# uac.net
KiCad netlist of a schematic drawn in EAGLE
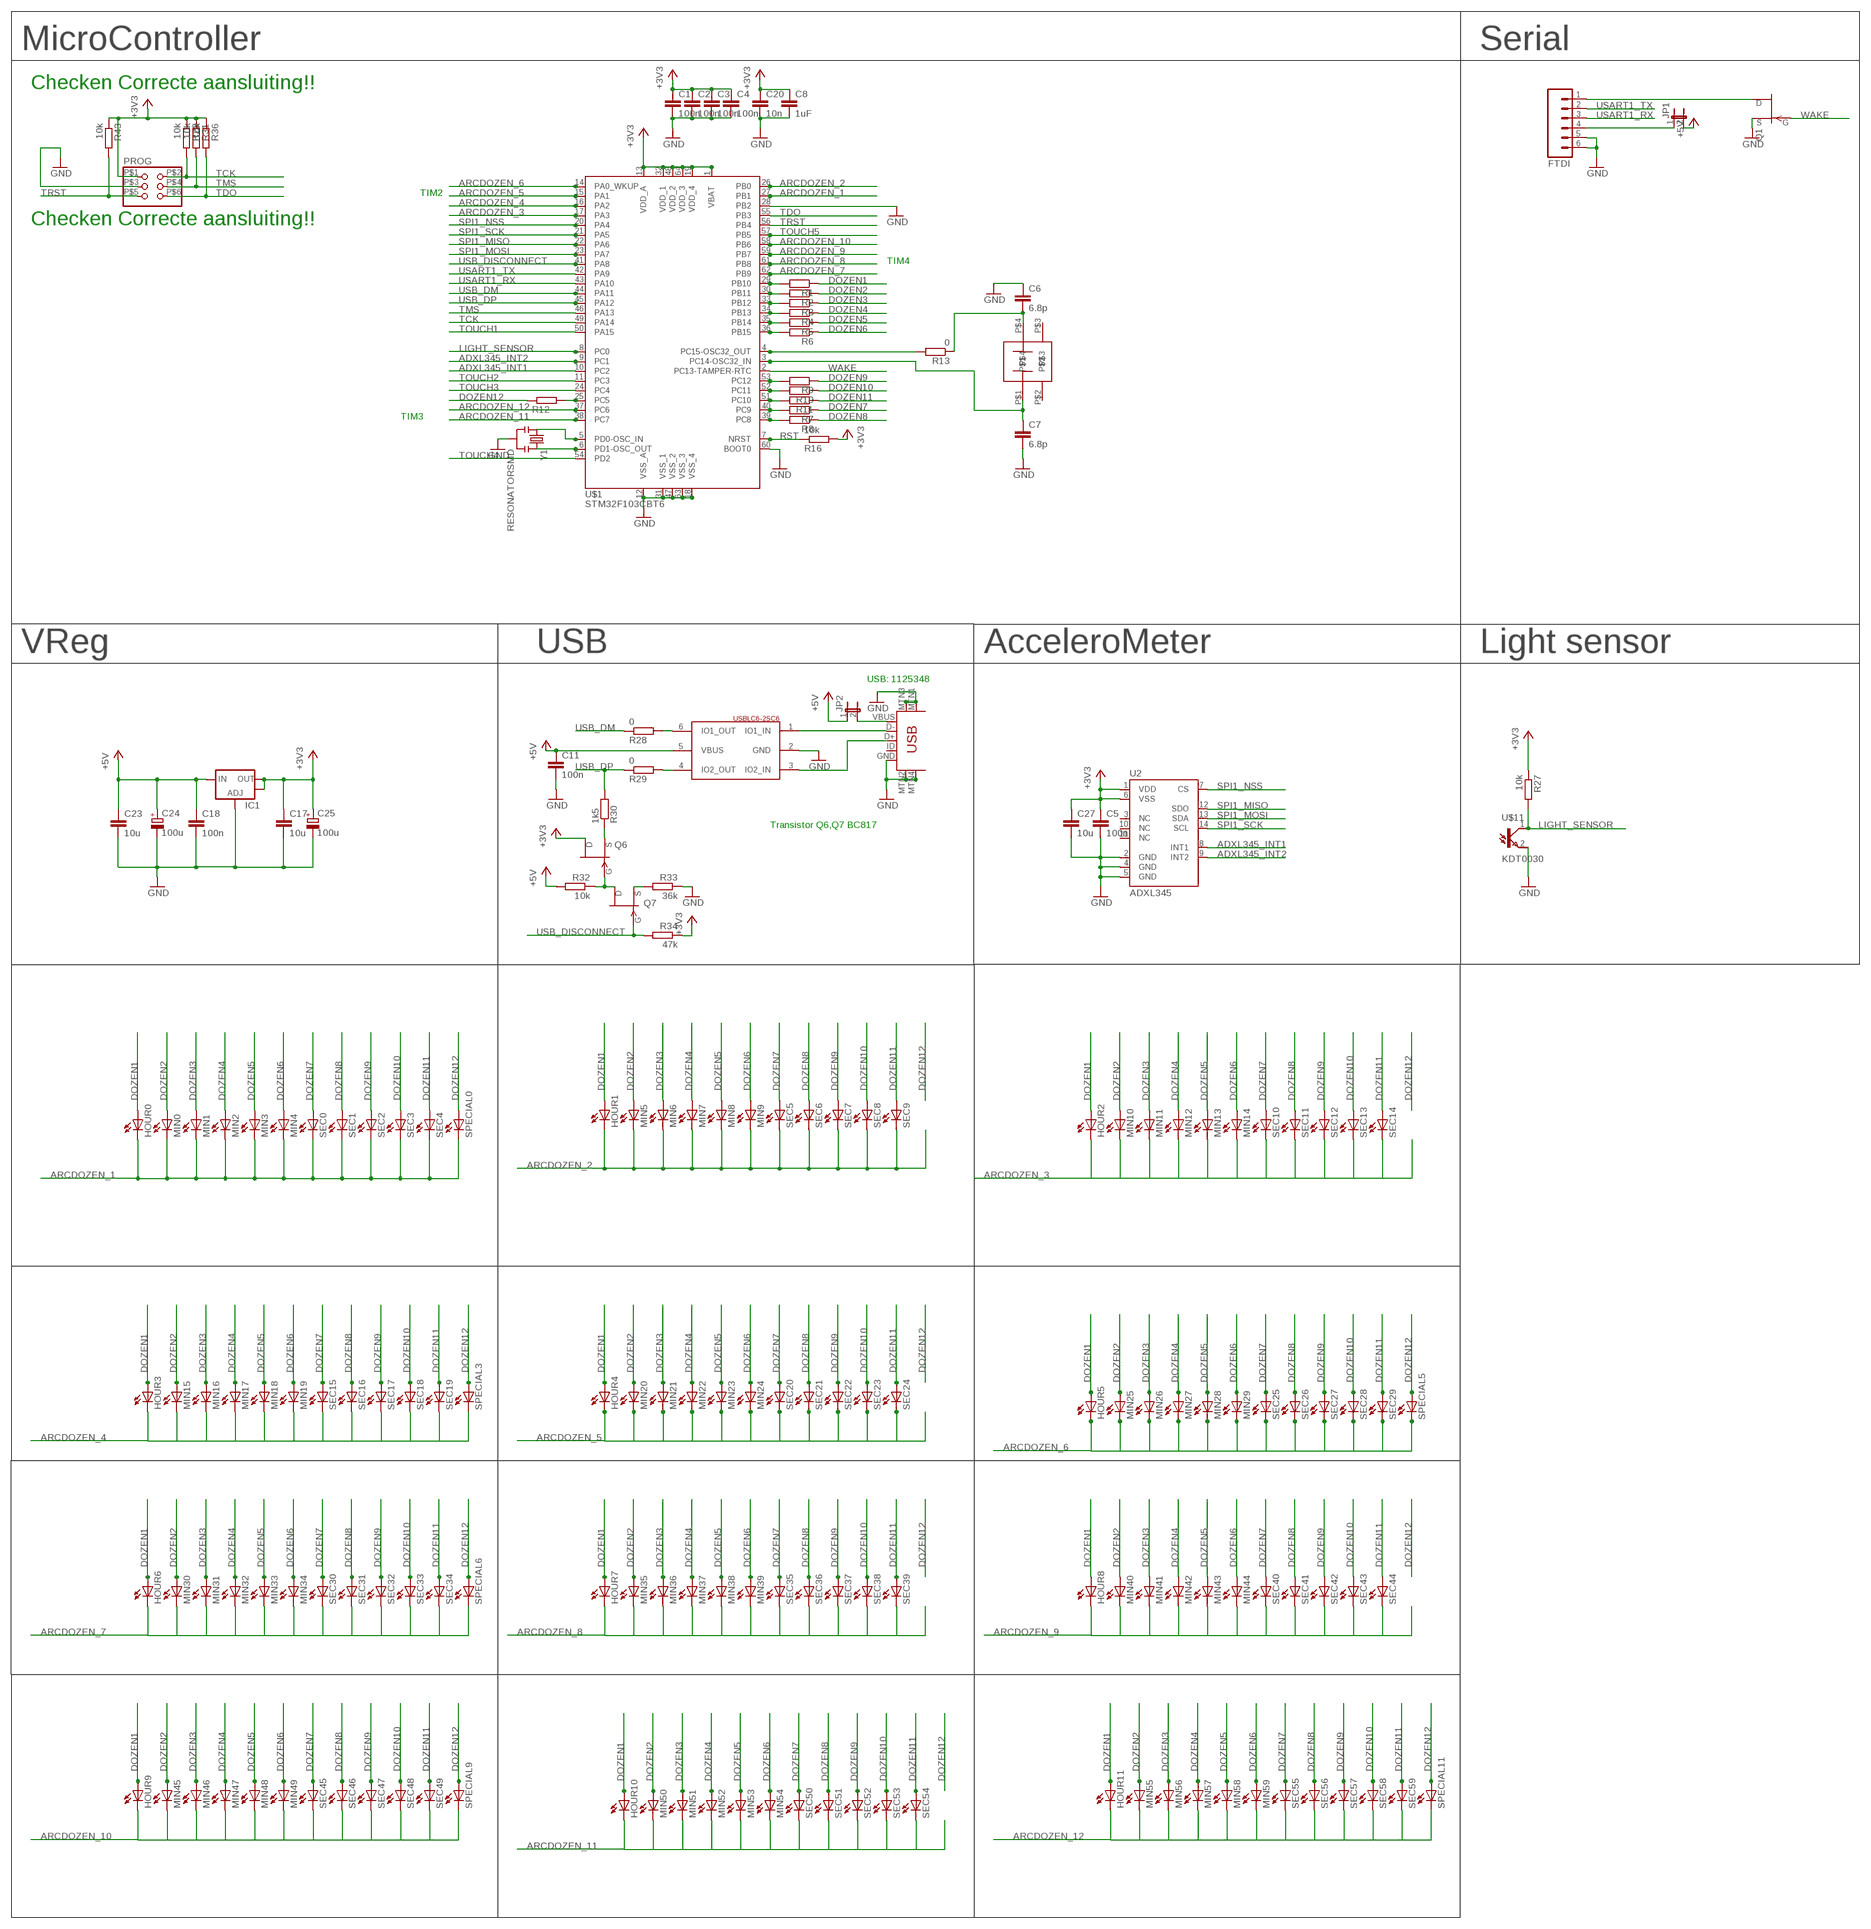
[diagram p0: schematic, sheet 1]

(export (version "E")
  (design (tool "Eeschema 10.0.6"))
  (components
    (comp (ref "C1")
      (value "100n")
      (footprint "eagle-import:C0603")
      (libsource (lib "eagle-import") (part "C-EUC0603"))
    )
    (comp (ref "C2")
      (value "100n")
      (footprint "eagle-import:C0603")
      (libsource (lib "eagle-import") (part "C-EUC0603"))
    )
    (comp (ref "C3")
      (value "100n")
      (footprint "eagle-import:C0603")
      (libsource (lib "eagle-import") (part "C-EUC0603"))
    )
    (comp (ref "C4")
      (value "100n")
      (footprint "eagle-import:C0603")
      (libsource (lib "eagle-import") (part "C-EUC0603"))
    )
    (comp (ref "C5")
      (value "100n")
      (footprint "eagle-import:C0603")
      (libsource (lib "eagle-import") (part "C-EUC0603"))
    )
    (comp (ref "C6")
      (value "6.8p")
      (footprint "eagle-import:C0603")
      (libsource (lib "eagle-import") (part "C-EUC0603"))
    )
    (comp (ref "C7")
      (value "6.8p")
      (footprint "eagle-import:C0603")
      (libsource (lib "eagle-import") (part "C-EUC0603"))
    )
    (comp (ref "C8")
      (value "1uF")
      (footprint "eagle-import:C0603")
      (libsource (lib "eagle-import") (part "C-EUC0603"))
    )
    (comp (ref "C11")
      (value "100n")
      (footprint "eagle-import:C0603")
      (libsource (lib "eagle-import") (part "C-EUC0603"))
    )
    (comp (ref "C17")
      (value "10u")
      (footprint "eagle-import:C0603")
      (libsource (lib "eagle-import") (part "C-EUC0603"))
    )
    (comp (ref "C18")
      (value "100n")
      (footprint "eagle-import:C0603")
      (libsource (lib "eagle-import") (part "C-EUC0603"))
    )
    (comp (ref "C20")
      (value "10n")
      (footprint "eagle-import:C0603")
      (libsource (lib "eagle-import") (part "C-EUC0603"))
    )
    (comp (ref "C23")
      (value "10u")
      (footprint "eagle-import:C0603")
      (libsource (lib "eagle-import") (part "C-EUC0603"))
    )
    (comp (ref "C24")
      (value "100u")
      (footprint "eagle-import:SMC_C")
      (libsource (lib "eagle-import") (part "CPOL-EUSMCC"))
    )
    (comp (ref "C25")
      (value "100u")
      (footprint "eagle-import:SMC_C")
      (libsource (lib "eagle-import") (part "CPOL-EUSMCC"))
    )
    (comp (ref "C27")
      (value "10u")
      (footprint "eagle-import:C0603")
      (libsource (lib "eagle-import") (part "C-EUC0603"))
    )
    (comp (ref "FTDI")
      (value "M06SMD")
      (footprint "eagle-import:1X06-SMD")
      (libsource (lib "eagle-import") (part "M06SMD"))
    )
    (comp (ref "HOUR0")
      (value "LEDCHIPLED_0603")
      (footprint "eagle-import:CHIPLED_0603")
      (libsource (lib "eagle-import") (part "LEDCHIPLED_0603"))
    )
    (comp (ref "HOUR1")
      (value "LEDCHIPLED_0603")
      (footprint "eagle-import:CHIPLED_0603")
      (libsource (lib "eagle-import") (part "LEDCHIPLED_0603"))
    )
    (comp (ref "HOUR2")
      (value "LEDCHIPLED_0603")
      (footprint "eagle-import:CHIPLED_0603")
      (libsource (lib "eagle-import") (part "LEDCHIPLED_0603"))
    )
    (comp (ref "HOUR3")
      (value "LEDCHIPLED_0603")
      (footprint "eagle-import:CHIPLED_0603")
      (libsource (lib "eagle-import") (part "LEDCHIPLED_0603"))
    )
    (comp (ref "HOUR4")
      (value "LEDCHIPLED_0603")
      (footprint "eagle-import:CHIPLED_0603")
      (libsource (lib "eagle-import") (part "LEDCHIPLED_0603"))
    )
    (comp (ref "HOUR5")
      (value "LEDCHIPLED_0603")
      (footprint "eagle-import:CHIPLED_0603")
      (libsource (lib "eagle-import") (part "LEDCHIPLED_0603"))
    )
    (comp (ref "HOUR6")
      (value "LEDCHIPLED_0603")
      (footprint "eagle-import:CHIPLED_0603")
      (libsource (lib "eagle-import") (part "LEDCHIPLED_0603"))
    )
    (comp (ref "HOUR7")
      (value "LEDCHIPLED_0603")
      (footprint "eagle-import:CHIPLED_0603")
      (libsource (lib "eagle-import") (part "LEDCHIPLED_0603"))
    )
    (comp (ref "HOUR8")
      (value "LEDCHIPLED_0603")
      (footprint "eagle-import:CHIPLED_0603")
      (libsource (lib "eagle-import") (part "LEDCHIPLED_0603"))
    )
    (comp (ref "HOUR9")
      (value "LEDCHIPLED_0603")
      (footprint "eagle-import:CHIPLED_0603")
      (libsource (lib "eagle-import") (part "LEDCHIPLED_0603"))
    )
    (comp (ref "HOUR10")
      (value "LEDCHIPLED_0603")
      (footprint "eagle-import:CHIPLED_0603")
      (libsource (lib "eagle-import") (part "LEDCHIPLED_0603"))
    )
    (comp (ref "HOUR11")
      (value "LEDCHIPLED_0603")
      (footprint "eagle-import:CHIPLED_0603")
      (libsource (lib "eagle-import") (part "LEDCHIPLED_0603"))
    )
    (comp (ref "IC1")
      (value "V_REG_LM1117SOT223")
      (footprint "eagle-import:SOT223")
      (libsource (lib "eagle-import") (part "V_REG_LM1117SOT223"))
    )
    (comp (ref "JP1")
      (value "JUMPER-2SMD-NO")
      (footprint "eagle-import:SJ_2S-NO")
      (libsource (lib "eagle-import") (part "JUMPER-2SMD-NO"))
    )
    (comp (ref "JP2")
      (value "JUMPER-2SMD-NO")
      (footprint "eagle-import:SJ_2S-NO")
      (libsource (lib "eagle-import") (part "JUMPER-2SMD-NO"))
    )
    (comp (ref "MIN0")
      (value "LEDCHIPLED_0603")
      (footprint "eagle-import:CHIPLED_0603")
      (libsource (lib "eagle-import") (part "LEDCHIPLED_0603"))
    )
    (comp (ref "MIN1")
      (value "LEDCHIPLED_0603")
      (footprint "eagle-import:CHIPLED_0603")
      (libsource (lib "eagle-import") (part "LEDCHIPLED_0603"))
    )
    (comp (ref "MIN2")
      (value "LEDCHIPLED_0603")
      (footprint "eagle-import:CHIPLED_0603")
      (libsource (lib "eagle-import") (part "LEDCHIPLED_0603"))
    )
    (comp (ref "MIN3")
      (value "LEDCHIPLED_0603")
      (footprint "eagle-import:CHIPLED_0603")
      (libsource (lib "eagle-import") (part "LEDCHIPLED_0603"))
    )
    (comp (ref "MIN4")
      (value "LEDCHIPLED_0603")
      (footprint "eagle-import:CHIPLED_0603")
      (libsource (lib "eagle-import") (part "LEDCHIPLED_0603"))
    )
    (comp (ref "MIN5")
      (value "LEDCHIPLED_0603")
      (footprint "eagle-import:CHIPLED_0603")
      (libsource (lib "eagle-import") (part "LEDCHIPLED_0603"))
    )
    (comp (ref "MIN6")
      (value "LEDCHIPLED_0603")
      (footprint "eagle-import:CHIPLED_0603")
      (libsource (lib "eagle-import") (part "LEDCHIPLED_0603"))
    )
    (comp (ref "MIN7")
      (value "LEDCHIPLED_0603")
      (footprint "eagle-import:CHIPLED_0603")
      (libsource (lib "eagle-import") (part "LEDCHIPLED_0603"))
    )
    (comp (ref "MIN8")
      (value "LEDCHIPLED_0603")
      (footprint "eagle-import:CHIPLED_0603")
      (libsource (lib "eagle-import") (part "LEDCHIPLED_0603"))
    )
    (comp (ref "MIN9")
      (value "LEDCHIPLED_0603")
      (footprint "eagle-import:CHIPLED_0603")
      (libsource (lib "eagle-import") (part "LEDCHIPLED_0603"))
    )
    (comp (ref "MIN10")
      (value "LEDCHIPLED_0603")
      (footprint "eagle-import:CHIPLED_0603")
      (libsource (lib "eagle-import") (part "LEDCHIPLED_0603"))
    )
    (comp (ref "MIN11")
      (value "LEDCHIPLED_0603")
      (footprint "eagle-import:CHIPLED_0603")
      (libsource (lib "eagle-import") (part "LEDCHIPLED_0603"))
    )
    (comp (ref "MIN12")
      (value "LEDCHIPLED_0603")
      (footprint "eagle-import:CHIPLED_0603")
      (libsource (lib "eagle-import") (part "LEDCHIPLED_0603"))
    )
    (comp (ref "MIN13")
      (value "LEDCHIPLED_0603")
      (footprint "eagle-import:CHIPLED_0603")
      (libsource (lib "eagle-import") (part "LEDCHIPLED_0603"))
    )
    (comp (ref "MIN14")
      (value "LEDCHIPLED_0603")
      (footprint "eagle-import:CHIPLED_0603")
      (libsource (lib "eagle-import") (part "LEDCHIPLED_0603"))
    )
    (comp (ref "MIN15")
      (value "LEDCHIPLED_0603")
      (footprint "eagle-import:CHIPLED_0603")
      (libsource (lib "eagle-import") (part "LEDCHIPLED_0603"))
    )
    (comp (ref "MIN16")
      (value "LEDCHIPLED_0603")
      (footprint "eagle-import:CHIPLED_0603")
      (libsource (lib "eagle-import") (part "LEDCHIPLED_0603"))
    )
    (comp (ref "MIN17")
      (value "LEDCHIPLED_0603")
      (footprint "eagle-import:CHIPLED_0603")
      (libsource (lib "eagle-import") (part "LEDCHIPLED_0603"))
    )
    (comp (ref "MIN18")
      (value "LEDCHIPLED_0603")
      (footprint "eagle-import:CHIPLED_0603")
      (libsource (lib "eagle-import") (part "LEDCHIPLED_0603"))
    )
    (comp (ref "MIN19")
      (value "LEDCHIPLED_0603")
      (footprint "eagle-import:CHIPLED_0603")
      (libsource (lib "eagle-import") (part "LEDCHIPLED_0603"))
    )
    (comp (ref "MIN20")
      (value "LEDCHIPLED_0603")
      (footprint "eagle-import:CHIPLED_0603")
      (libsource (lib "eagle-import") (part "LEDCHIPLED_0603"))
    )
    (comp (ref "MIN21")
      (value "LEDCHIPLED_0603")
      (footprint "eagle-import:CHIPLED_0603")
      (libsource (lib "eagle-import") (part "LEDCHIPLED_0603"))
    )
    (comp (ref "MIN22")
      (value "LEDCHIPLED_0603")
      (footprint "eagle-import:CHIPLED_0603")
      (libsource (lib "eagle-import") (part "LEDCHIPLED_0603"))
    )
    (comp (ref "MIN23")
      (value "LEDCHIPLED_0603")
      (footprint "eagle-import:CHIPLED_0603")
      (libsource (lib "eagle-import") (part "LEDCHIPLED_0603"))
    )
    (comp (ref "MIN24")
      (value "LEDCHIPLED_0603")
      (footprint "eagle-import:CHIPLED_0603")
      (libsource (lib "eagle-import") (part "LEDCHIPLED_0603"))
    )
    (comp (ref "MIN25")
      (value "LEDCHIPLED_0603")
      (footprint "eagle-import:CHIPLED_0603")
      (libsource (lib "eagle-import") (part "LEDCHIPLED_0603"))
    )
    (comp (ref "MIN26")
      (value "LEDCHIPLED_0603")
      (footprint "eagle-import:CHIPLED_0603")
      (libsource (lib "eagle-import") (part "LEDCHIPLED_0603"))
    )
    (comp (ref "MIN27")
      (value "LEDCHIPLED_0603")
      (footprint "eagle-import:CHIPLED_0603")
      (libsource (lib "eagle-import") (part "LEDCHIPLED_0603"))
    )
    (comp (ref "MIN28")
      (value "LEDCHIPLED_0603")
      (footprint "eagle-import:CHIPLED_0603")
      (libsource (lib "eagle-import") (part "LEDCHIPLED_0603"))
    )
    (comp (ref "MIN29")
      (value "LEDCHIPLED_0603")
      (footprint "eagle-import:CHIPLED_0603")
      (libsource (lib "eagle-import") (part "LEDCHIPLED_0603"))
    )
    (comp (ref "MIN30")
      (value "LEDCHIPLED_0603")
      (footprint "eagle-import:CHIPLED_0603")
      (libsource (lib "eagle-import") (part "LEDCHIPLED_0603"))
    )
    (comp (ref "MIN31")
      (value "LEDCHIPLED_0603")
      (footprint "eagle-import:CHIPLED_0603")
      (libsource (lib "eagle-import") (part "LEDCHIPLED_0603"))
    )
    (comp (ref "MIN32")
      (value "LEDCHIPLED_0603")
      (footprint "eagle-import:CHIPLED_0603")
      (libsource (lib "eagle-import") (part "LEDCHIPLED_0603"))
    )
    (comp (ref "MIN33")
      (value "LEDCHIPLED_0603")
      (footprint "eagle-import:CHIPLED_0603")
      (libsource (lib "eagle-import") (part "LEDCHIPLED_0603"))
    )
    (comp (ref "MIN34")
      (value "LEDCHIPLED_0603")
      (footprint "eagle-import:CHIPLED_0603")
      (libsource (lib "eagle-import") (part "LEDCHIPLED_0603"))
    )
    (comp (ref "MIN35")
      (value "LEDCHIPLED_0603")
      (footprint "eagle-import:CHIPLED_0603")
      (libsource (lib "eagle-import") (part "LEDCHIPLED_0603"))
    )
    (comp (ref "MIN36")
      (value "LEDCHIPLED_0603")
      (footprint "eagle-import:CHIPLED_0603")
      (libsource (lib "eagle-import") (part "LEDCHIPLED_0603"))
    )
    (comp (ref "MIN37")
      (value "LEDCHIPLED_0603")
      (footprint "eagle-import:CHIPLED_0603")
      (libsource (lib "eagle-import") (part "LEDCHIPLED_0603"))
    )
    (comp (ref "MIN38")
      (value "LEDCHIPLED_0603")
      (footprint "eagle-import:CHIPLED_0603")
      (libsource (lib "eagle-import") (part "LEDCHIPLED_0603"))
    )
    (comp (ref "MIN39")
      (value "LEDCHIPLED_0603")
      (footprint "eagle-import:CHIPLED_0603")
      (libsource (lib "eagle-import") (part "LEDCHIPLED_0603"))
    )
    (comp (ref "MIN40")
      (value "LEDCHIPLED_0603")
      (footprint "eagle-import:CHIPLED_0603")
      (libsource (lib "eagle-import") (part "LEDCHIPLED_0603"))
    )
    (comp (ref "MIN41")
      (value "LEDCHIPLED_0603")
      (footprint "eagle-import:CHIPLED_0603")
      (libsource (lib "eagle-import") (part "LEDCHIPLED_0603"))
    )
    (comp (ref "MIN42")
      (value "LEDCHIPLED_0603")
      (footprint "eagle-import:CHIPLED_0603")
      (libsource (lib "eagle-import") (part "LEDCHIPLED_0603"))
    )
    (comp (ref "MIN43")
      (value "LEDCHIPLED_0603")
      (footprint "eagle-import:CHIPLED_0603")
      (libsource (lib "eagle-import") (part "LEDCHIPLED_0603"))
    )
    (comp (ref "MIN44")
      (value "LEDCHIPLED_0603")
      (footprint "eagle-import:CHIPLED_0603")
      (libsource (lib "eagle-import") (part "LEDCHIPLED_0603"))
    )
    (comp (ref "MIN45")
      (value "LEDCHIPLED_0603")
      (footprint "eagle-import:CHIPLED_0603")
      (libsource (lib "eagle-import") (part "LEDCHIPLED_0603"))
    )
    (comp (ref "MIN46")
      (value "LEDCHIPLED_0603")
      (footprint "eagle-import:CHIPLED_0603")
      (libsource (lib "eagle-import") (part "LEDCHIPLED_0603"))
    )
    (comp (ref "MIN47")
      (value "LEDCHIPLED_0603")
      (footprint "eagle-import:CHIPLED_0603")
      (libsource (lib "eagle-import") (part "LEDCHIPLED_0603"))
    )
    (comp (ref "MIN48")
      (value "LEDCHIPLED_0603")
      (footprint "eagle-import:CHIPLED_0603")
      (libsource (lib "eagle-import") (part "LEDCHIPLED_0603"))
    )
    (comp (ref "MIN49")
      (value "LEDCHIPLED_0603")
      (footprint "eagle-import:CHIPLED_0603")
      (libsource (lib "eagle-import") (part "LEDCHIPLED_0603"))
    )
    (comp (ref "MIN50")
      (value "LEDCHIPLED_0603")
      (footprint "eagle-import:CHIPLED_0603")
      (libsource (lib "eagle-import") (part "LEDCHIPLED_0603"))
    )
    (comp (ref "MIN51")
      (value "LEDCHIPLED_0603")
      (footprint "eagle-import:CHIPLED_0603")
      (libsource (lib "eagle-import") (part "LEDCHIPLED_0603"))
    )
    (comp (ref "MIN52")
      (value "LEDCHIPLED_0603")
      (footprint "eagle-import:CHIPLED_0603")
      (libsource (lib "eagle-import") (part "LEDCHIPLED_0603"))
    )
    (comp (ref "MIN53")
      (value "LEDCHIPLED_0603")
      (footprint "eagle-import:CHIPLED_0603")
      (libsource (lib "eagle-import") (part "LEDCHIPLED_0603"))
    )
    (comp (ref "MIN54")
      (value "LEDCHIPLED_0603")
      (footprint "eagle-import:CHIPLED_0603")
      (libsource (lib "eagle-import") (part "LEDCHIPLED_0603"))
    )
    (comp (ref "MIN55")
      (value "LEDCHIPLED_0603")
      (footprint "eagle-import:CHIPLED_0603")
      (libsource (lib "eagle-import") (part "LEDCHIPLED_0603"))
    )
    (comp (ref "MIN56")
      (value "LEDCHIPLED_0603")
      (footprint "eagle-import:CHIPLED_0603")
      (libsource (lib "eagle-import") (part "LEDCHIPLED_0603"))
    )
    (comp (ref "MIN57")
      (value "LEDCHIPLED_0603")
      (footprint "eagle-import:CHIPLED_0603")
      (libsource (lib "eagle-import") (part "LEDCHIPLED_0603"))
    )
    (comp (ref "MIN58")
      (value "LEDCHIPLED_0603")
      (footprint "eagle-import:CHIPLED_0603")
      (libsource (lib "eagle-import") (part "LEDCHIPLED_0603"))
    )
    (comp (ref "MIN59")
      (value "LEDCHIPLED_0603")
      (footprint "eagle-import:CHIPLED_0603")
      (libsource (lib "eagle-import") (part "LEDCHIPLED_0603"))
    )
    (comp (ref "PROG")
      (value "PINHD-2X3SMT")
      (footprint "eagle-import:2X03_SMT")
      (libsource (lib "eagle-import") (part "PINHD-2X3SMT"))
    )
    (comp (ref "Q1")
      (value "2N7002CK4SST")
      (footprint "eagle-import:SOT23")
      (libsource (lib "eagle-import") (part "2N7002CKSST4"))
    )
    (comp (ref "Q6")
      (value "2N7002CK4SST")
      (footprint "eagle-import:SOT23")
      (libsource (lib "eagle-import") (part "2N7002CKSST4"))
    )
    (comp (ref "Q7")
      (value "2N7002CK4SST")
      (footprint "eagle-import:SOT23")
      (libsource (lib "eagle-import") (part "2N7002CKSST4"))
    )
    (comp (ref "R1")
      (value "R-EU_R0603")
      (footprint "eagle-import:R0603")
      (libsource (lib "eagle-import") (part "R-EU_R0603"))
    )
    (comp (ref "R2")
      (value "R-EU_R0603")
      (footprint "eagle-import:R0603")
      (libsource (lib "eagle-import") (part "R-EU_R0603"))
    )
    (comp (ref "R3")
      (value "R-EU_R0603")
      (footprint "eagle-import:R0603")
      (libsource (lib "eagle-import") (part "R-EU_R0603"))
    )
    (comp (ref "R4")
      (value "R-EU_R0603")
      (footprint "eagle-import:R0603")
      (libsource (lib "eagle-import") (part "R-EU_R0603"))
    )
    (comp (ref "R5")
      (value "R-EU_R0603")
      (footprint "eagle-import:R0603")
      (libsource (lib "eagle-import") (part "R-EU_R0603"))
    )
    (comp (ref "R6")
      (value "R-EU_R0603")
      (footprint "eagle-import:R0603")
      (libsource (lib "eagle-import") (part "R-EU_R0603"))
    )
    (comp (ref "R7")
      (value "R-EU_R0603")
      (footprint "eagle-import:R0603")
      (libsource (lib "eagle-import") (part "R-EU_R0603"))
    )
    (comp (ref "R8")
      (value "R-EU_R0603")
      (footprint "eagle-import:R0603")
      (libsource (lib "eagle-import") (part "R-EU_R0603"))
    )
    (comp (ref "R9")
      (value "R-EU_R0603")
      (footprint "eagle-import:R0603")
      (libsource (lib "eagle-import") (part "R-EU_R0603"))
    )
    (comp (ref "R10")
      (value "R-EU_R0603")
      (footprint "eagle-import:R0603")
      (libsource (lib "eagle-import") (part "R-EU_R0603"))
    )
    (comp (ref "R11")
      (value "R-EU_R0603")
      (footprint "eagle-import:R0603")
      (libsource (lib "eagle-import") (part "R-EU_R0603"))
    )
    (comp (ref "R12")
      (value "R-EU_R0603")
      (footprint "eagle-import:R0603")
      (libsource (lib "eagle-import") (part "R-EU_R0603"))
    )
    (comp (ref "R13")
      (value "0")
      (footprint "eagle-import:R0603")
      (libsource (lib "eagle-import") (part "R-EU_R0603"))
    )
    (comp (ref "R16")
      (value "10k")
      (footprint "eagle-import:R0603")
      (libsource (lib "eagle-import") (part "R-EU_R0603"))
    )
    (comp (ref "R23")
      (value "10k")
      (footprint "eagle-import:R0603")
      (libsource (lib "eagle-import") (part "R-EU_R0603"))
    )
    (comp (ref "R27")
      (value "10k")
      (footprint "eagle-import:R0603")
      (libsource (lib "eagle-import") (part "R-EU_R0603"))
    )
    (comp (ref "R28")
      (value "0")
      (footprint "eagle-import:R0603")
      (libsource (lib "eagle-import") (part "R-EU_R0603"))
    )
    (comp (ref "R29")
      (value "0")
      (footprint "eagle-import:R0603")
      (libsource (lib "eagle-import") (part "R-EU_R0603"))
    )
    (comp (ref "R30")
      (value "1k5")
      (footprint "eagle-import:R0603")
      (libsource (lib "eagle-import") (part "R-EU_R0603"))
    )
    (comp (ref "R31")
      (value "10k")
      (footprint "eagle-import:R0603")
      (libsource (lib "eagle-import") (part "R-EU_R0603"))
    )
    (comp (ref "R32")
      (value "10k")
      (footprint "eagle-import:R0603")
      (libsource (lib "eagle-import") (part "R-EU_R0603"))
    )
    (comp (ref "R33")
      (value "36k")
      (footprint "eagle-import:R0603")
      (libsource (lib "eagle-import") (part "R-EU_R0603"))
    )
    (comp (ref "R34")
      (value "47k")
      (footprint "eagle-import:R0603")
      (libsource (lib "eagle-import") (part "R-EU_R0603"))
    )
    (comp (ref "R36")
      (value "10k")
      (footprint "eagle-import:R0603")
      (libsource (lib "eagle-import") (part "R-EU_R0603"))
    )
    (comp (ref "R43")
      (value "10k")
      (footprint "eagle-import:R0603")
      (libsource (lib "eagle-import") (part "R-EU_R0603"))
    )
    (comp (ref "SEC0")
      (value "LEDCHIPLED_0603")
      (footprint "eagle-import:CHIPLED_0603")
      (libsource (lib "eagle-import") (part "LEDCHIPLED_0603"))
    )
    (comp (ref "SEC1")
      (value "LEDCHIPLED_0603")
      (footprint "eagle-import:CHIPLED_0603")
      (libsource (lib "eagle-import") (part "LEDCHIPLED_0603"))
    )
    (comp (ref "SEC2")
      (value "LEDCHIPLED_0603")
      (footprint "eagle-import:CHIPLED_0603")
      (libsource (lib "eagle-import") (part "LEDCHIPLED_0603"))
    )
    (comp (ref "SEC3")
      (value "LEDCHIPLED_0603")
      (footprint "eagle-import:CHIPLED_0603")
      (libsource (lib "eagle-import") (part "LEDCHIPLED_0603"))
    )
    (comp (ref "SEC4")
      (value "LEDCHIPLED_0603")
      (footprint "eagle-import:CHIPLED_0603")
      (libsource (lib "eagle-import") (part "LEDCHIPLED_0603"))
    )
    (comp (ref "SEC5")
      (value "LEDCHIPLED_0603")
      (footprint "eagle-import:CHIPLED_0603")
      (libsource (lib "eagle-import") (part "LEDCHIPLED_0603"))
    )
    (comp (ref "SEC6")
      (value "LEDCHIPLED_0603")
      (footprint "eagle-import:CHIPLED_0603")
      (libsource (lib "eagle-import") (part "LEDCHIPLED_0603"))
    )
    (comp (ref "SEC7")
      (value "LEDCHIPLED_0603")
      (footprint "eagle-import:CHIPLED_0603")
      (libsource (lib "eagle-import") (part "LEDCHIPLED_0603"))
    )
    (comp (ref "SEC8")
      (value "LEDCHIPLED_0603")
      (footprint "eagle-import:CHIPLED_0603")
      (libsource (lib "eagle-import") (part "LEDCHIPLED_0603"))
    )
    (comp (ref "SEC9")
      (value "LEDCHIPLED_0603")
      (footprint "eagle-import:CHIPLED_0603")
      (libsource (lib "eagle-import") (part "LEDCHIPLED_0603"))
    )
    (comp (ref "SEC10")
      (value "LEDCHIPLED_0603")
      (footprint "eagle-import:CHIPLED_0603")
      (libsource (lib "eagle-import") (part "LEDCHIPLED_0603"))
    )
    (comp (ref "SEC11")
      (value "LEDCHIPLED_0603")
      (footprint "eagle-import:CHIPLED_0603")
      (libsource (lib "eagle-import") (part "LEDCHIPLED_0603"))
    )
    (comp (ref "SEC12")
      (value "LEDCHIPLED_0603")
      (footprint "eagle-import:CHIPLED_0603")
      (libsource (lib "eagle-import") (part "LEDCHIPLED_0603"))
    )
    (comp (ref "SEC13")
      (value "LEDCHIPLED_0603")
      (footprint "eagle-import:CHIPLED_0603")
      (libsource (lib "eagle-import") (part "LEDCHIPLED_0603"))
    )
    (comp (ref "SEC14")
      (value "LEDCHIPLED_0603")
      (footprint "eagle-import:CHIPLED_0603")
      (libsource (lib "eagle-import") (part "LEDCHIPLED_0603"))
    )
    (comp (ref "SEC15")
      (value "LEDCHIPLED_0603")
      (footprint "eagle-import:CHIPLED_0603")
      (libsource (lib "eagle-import") (part "LEDCHIPLED_0603"))
    )
    (comp (ref "SEC16")
      (value "LEDCHIPLED_0603")
      (footprint "eagle-import:CHIPLED_0603")
      (libsource (lib "eagle-import") (part "LEDCHIPLED_0603"))
    )
    (comp (ref "SEC17")
      (value "LEDCHIPLED_0603")
      (footprint "eagle-import:CHIPLED_0603")
      (libsource (lib "eagle-import") (part "LEDCHIPLED_0603"))
    )
    (comp (ref "SEC18")
      (value "LEDCHIPLED_0603")
      (footprint "eagle-import:CHIPLED_0603")
      (libsource (lib "eagle-import") (part "LEDCHIPLED_0603"))
    )
    (comp (ref "SEC19")
      (value "LEDCHIPLED_0603")
      (footprint "eagle-import:CHIPLED_0603")
      (libsource (lib "eagle-import") (part "LEDCHIPLED_0603"))
    )
    (comp (ref "SEC20")
      (value "LEDCHIPLED_0603")
      (footprint "eagle-import:CHIPLED_0603")
      (libsource (lib "eagle-import") (part "LEDCHIPLED_0603"))
    )
    (comp (ref "SEC21")
      (value "LEDCHIPLED_0603")
      (footprint "eagle-import:CHIPLED_0603")
      (libsource (lib "eagle-import") (part "LEDCHIPLED_0603"))
    )
    (comp (ref "SEC22")
      (value "LEDCHIPLED_0603")
      (footprint "eagle-import:CHIPLED_0603")
      (libsource (lib "eagle-import") (part "LEDCHIPLED_0603"))
    )
    (comp (ref "SEC23")
      (value "LEDCHIPLED_0603")
      (footprint "eagle-import:CHIPLED_0603")
      (libsource (lib "eagle-import") (part "LEDCHIPLED_0603"))
    )
    (comp (ref "SEC24")
      (value "LEDCHIPLED_0603")
      (footprint "eagle-import:CHIPLED_0603")
      (libsource (lib "eagle-import") (part "LEDCHIPLED_0603"))
    )
    (comp (ref "SEC25")
      (value "LEDCHIPLED_0603")
      (footprint "eagle-import:CHIPLED_0603")
      (libsource (lib "eagle-import") (part "LEDCHIPLED_0603"))
    )
    (comp (ref "SEC26")
      (value "LEDCHIPLED_0603")
      (footprint "eagle-import:CHIPLED_0603")
      (libsource (lib "eagle-import") (part "LEDCHIPLED_0603"))
    )
    (comp (ref "SEC27")
      (value "LEDCHIPLED_0603")
      (footprint "eagle-import:CHIPLED_0603")
      (libsource (lib "eagle-import") (part "LEDCHIPLED_0603"))
    )
    (comp (ref "SEC28")
      (value "LEDCHIPLED_0603")
      (footprint "eagle-import:CHIPLED_0603")
      (libsource (lib "eagle-import") (part "LEDCHIPLED_0603"))
    )
    (comp (ref "SEC29")
      (value "LEDCHIPLED_0603")
      (footprint "eagle-import:CHIPLED_0603")
      (libsource (lib "eagle-import") (part "LEDCHIPLED_0603"))
    )
    (comp (ref "SEC30")
      (value "LEDCHIPLED_0603")
      (footprint "eagle-import:CHIPLED_0603")
      (libsource (lib "eagle-import") (part "LEDCHIPLED_0603"))
    )
    (comp (ref "SEC31")
      (value "LEDCHIPLED_0603")
      (footprint "eagle-import:CHIPLED_0603")
      (libsource (lib "eagle-import") (part "LEDCHIPLED_0603"))
    )
    (comp (ref "SEC32")
      (value "LEDCHIPLED_0603")
      (footprint "eagle-import:CHIPLED_0603")
      (libsource (lib "eagle-import") (part "LEDCHIPLED_0603"))
    )
    (comp (ref "SEC33")
      (value "LEDCHIPLED_0603")
      (footprint "eagle-import:CHIPLED_0603")
      (libsource (lib "eagle-import") (part "LEDCHIPLED_0603"))
    )
    (comp (ref "SEC34")
      (value "LEDCHIPLED_0603")
      (footprint "eagle-import:CHIPLED_0603")
      (libsource (lib "eagle-import") (part "LEDCHIPLED_0603"))
    )
    (comp (ref "SEC35")
      (value "LEDCHIPLED_0603")
      (footprint "eagle-import:CHIPLED_0603")
      (libsource (lib "eagle-import") (part "LEDCHIPLED_0603"))
    )
    (comp (ref "SEC36")
      (value "LEDCHIPLED_0603")
      (footprint "eagle-import:CHIPLED_0603")
      (libsource (lib "eagle-import") (part "LEDCHIPLED_0603"))
    )
    (comp (ref "SEC37")
      (value "LEDCHIPLED_0603")
      (footprint "eagle-import:CHIPLED_0603")
      (libsource (lib "eagle-import") (part "LEDCHIPLED_0603"))
    )
    (comp (ref "SEC38")
      (value "LEDCHIPLED_0603")
      (footprint "eagle-import:CHIPLED_0603")
      (libsource (lib "eagle-import") (part "LEDCHIPLED_0603"))
    )
    (comp (ref "SEC39")
      (value "LEDCHIPLED_0603")
      (footprint "eagle-import:CHIPLED_0603")
      (libsource (lib "eagle-import") (part "LEDCHIPLED_0603"))
    )
    (comp (ref "SEC40")
      (value "LEDCHIPLED_0603")
      (footprint "eagle-import:CHIPLED_0603")
      (libsource (lib "eagle-import") (part "LEDCHIPLED_0603"))
    )
    (comp (ref "SEC41")
      (value "LEDCHIPLED_0603")
      (footprint "eagle-import:CHIPLED_0603")
      (libsource (lib "eagle-import") (part "LEDCHIPLED_0603"))
    )
    (comp (ref "SEC42")
      (value "LEDCHIPLED_0603")
      (footprint "eagle-import:CHIPLED_0603")
      (libsource (lib "eagle-import") (part "LEDCHIPLED_0603"))
    )
    (comp (ref "SEC43")
      (value "LEDCHIPLED_0603")
      (footprint "eagle-import:CHIPLED_0603")
      (libsource (lib "eagle-import") (part "LEDCHIPLED_0603"))
    )
    (comp (ref "SEC44")
      (value "LEDCHIPLED_0603")
      (footprint "eagle-import:CHIPLED_0603")
      (libsource (lib "eagle-import") (part "LEDCHIPLED_0603"))
    )
    (comp (ref "SEC45")
      (value "LEDCHIPLED_0603")
      (footprint "eagle-import:CHIPLED_0603")
      (libsource (lib "eagle-import") (part "LEDCHIPLED_0603"))
    )
    (comp (ref "SEC46")
      (value "LEDCHIPLED_0603")
      (footprint "eagle-import:CHIPLED_0603")
      (libsource (lib "eagle-import") (part "LEDCHIPLED_0603"))
    )
    (comp (ref "SEC47")
      (value "LEDCHIPLED_0603")
      (footprint "eagle-import:CHIPLED_0603")
      (libsource (lib "eagle-import") (part "LEDCHIPLED_0603"))
    )
    (comp (ref "SEC48")
      (value "LEDCHIPLED_0603")
      (footprint "eagle-import:CHIPLED_0603")
      (libsource (lib "eagle-import") (part "LEDCHIPLED_0603"))
    )
    (comp (ref "SEC49")
      (value "LEDCHIPLED_0603")
      (footprint "eagle-import:CHIPLED_0603")
      (libsource (lib "eagle-import") (part "LEDCHIPLED_0603"))
    )
    (comp (ref "SEC50")
      (value "LEDCHIPLED_0603")
      (footprint "eagle-import:CHIPLED_0603")
      (libsource (lib "eagle-import") (part "LEDCHIPLED_0603"))
    )
    (comp (ref "SEC51")
      (value "LEDCHIPLED_0603")
      (footprint "eagle-import:CHIPLED_0603")
      (libsource (lib "eagle-import") (part "LEDCHIPLED_0603"))
    )
    (comp (ref "SEC52")
      (value "LEDCHIPLED_0603")
      (footprint "eagle-import:CHIPLED_0603")
      (libsource (lib "eagle-import") (part "LEDCHIPLED_0603"))
    )
    (comp (ref "SEC53")
      (value "LEDCHIPLED_0603")
      (footprint "eagle-import:CHIPLED_0603")
      (libsource (lib "eagle-import") (part "LEDCHIPLED_0603"))
    )
    (comp (ref "SEC54")
      (value "LEDCHIPLED_0603")
      (footprint "eagle-import:CHIPLED_0603")
      (libsource (lib "eagle-import") (part "LEDCHIPLED_0603"))
    )
    (comp (ref "SEC55")
      (value "LEDCHIPLED_0603")
      (footprint "eagle-import:CHIPLED_0603")
      (libsource (lib "eagle-import") (part "LEDCHIPLED_0603"))
    )
    (comp (ref "SEC56")
      (value "LEDCHIPLED_0603")
      (footprint "eagle-import:CHIPLED_0603")
      (libsource (lib "eagle-import") (part "LEDCHIPLED_0603"))
    )
    (comp (ref "SEC57")
      (value "LEDCHIPLED_0603")
      (footprint "eagle-import:CHIPLED_0603")
      (libsource (lib "eagle-import") (part "LEDCHIPLED_0603"))
    )
    (comp (ref "SEC58")
      (value "LEDCHIPLED_0603")
      (footprint "eagle-import:CHIPLED_0603")
      (libsource (lib "eagle-import") (part "LEDCHIPLED_0603"))
    )
    (comp (ref "SEC59")
      (value "LEDCHIPLED_0603")
      (footprint "eagle-import:CHIPLED_0603")
      (libsource (lib "eagle-import") (part "LEDCHIPLED_0603"))
    )
    (comp (ref "SPECIAL0")
      (value "LEDCHIPLED_0603")
      (footprint "eagle-import:CHIPLED_0603")
      (libsource (lib "eagle-import") (part "LEDCHIPLED_0603"))
    )
    (comp (ref "SPECIAL3")
      (value "LEDCHIPLED_0603")
      (footprint "eagle-import:CHIPLED_0603")
      (libsource (lib "eagle-import") (part "LEDCHIPLED_0603"))
    )
    (comp (ref "SPECIAL5")
      (value "LEDCHIPLED_0603")
      (footprint "eagle-import:CHIPLED_0603")
      (libsource (lib "eagle-import") (part "LEDCHIPLED_0603"))
    )
    (comp (ref "SPECIAL6")
      (value "LEDCHIPLED_0603")
      (footprint "eagle-import:CHIPLED_0603")
      (libsource (lib "eagle-import") (part "LEDCHIPLED_0603"))
    )
    (comp (ref "SPECIAL9")
      (value "LEDCHIPLED_0603")
      (footprint "eagle-import:CHIPLED_0603")
      (libsource (lib "eagle-import") (part "LEDCHIPLED_0603"))
    )
    (comp (ref "SPECIAL11")
      (value "LEDCHIPLED_0603")
      (footprint "eagle-import:CHIPLED_0603")
      (libsource (lib "eagle-import") (part "LEDCHIPLED_0603"))
    )
    (comp (ref "U$1")
      (value "STM32F103CBT6")
      (footprint "eagle-import:LQFP64")
      (libsource (lib "eagle-import") (part "STM32F103CBT6"))
    )
    (comp (ref "U$2")
      (value "CRYSTAL_32KHZ")
      (footprint "eagle-import:CRYSTAL_32KHZ")
      (fields (field (name "MPN") "MC-306 32.768K-E3:ROHS"))
      (libsource (lib "eagle-import") (part "CRYSTAL_32KHZ"))
    )
    (comp (ref "U$11")
      (value "KDT0030")
      (footprint "eagle-import:FLD00030")
      (fields (field (name "MPN") "KDT00030TR"))
      (libsource (lib "eagle-import") (part "KDT0030"))
    )
    (comp (ref "U$12")
      (value "USB-MINIB-5PIN")
      (footprint "eagle-import:USB-MINIB")
      (libsource (lib "eagle-import") (part "USB-MINIB-5PIN"))
    )
    (comp (ref "U$13")
      (value "USBLC6-2SC6")
      (footprint "eagle-import:SOT23")
      (libsource (lib "eagle-import") (part "USBLC6-2SC6"))
    )
    (comp (ref "U2")
      (value "ADXL345")
      (footprint "eagle-import:LGA14")
      (libsource (lib "eagle-import") (part "ADXL345"))
    )
    (comp (ref "Y1")
      (value "RESONATORSMD")
      (footprint "eagle-import:RESONATOR-SMD")
      (libsource (lib "eagle-import") (part "RESONATORSMD"))
    )
  )
  (nets
    (net (code "1") (name "+3V3") (class "Default")
      (node (ref "C1") (pin "1") (pinfunction "1_1") (pintype "passive"))
      (node (ref "C17") (pin "1") (pinfunction "1_1") (pintype "passive"))
      (node (ref "C2") (pin "1") (pinfunction "1_1") (pintype "passive"))
      (node (ref "C20") (pin "1") (pinfunction "1_1") (pintype "passive"))
      (node (ref "C25") (pin "+") (pinfunction "+_+") (pintype "passive"))
      (node (ref "C27") (pin "1") (pinfunction "1_1") (pintype "passive"))
      (node (ref "C3") (pin "1") (pinfunction "1_1") (pintype "passive"))
      (node (ref "C4") (pin "1") (pinfunction "1_1") (pintype "passive"))
      (node (ref "C5") (pin "1") (pinfunction "1_1") (pintype "passive"))
      (node (ref "C8") (pin "1") (pinfunction "1_1") (pintype "passive"))
      (node (ref "IC1") (pin "2") (pinfunction "OUT_2") (pintype "output"))
      (node (ref "IC1") (pin "4") (pinfunction "OUT_4") (pintype "output"))
      (node (ref "PROG") (pin "P$1") (pinfunction "1_P$1") (pintype "passive"))
      (node (ref "Q6") (pin "3") (pinfunction "D_3") (pintype "passive"))
      (node (ref "R16") (pin "2") (pinfunction "2_2") (pintype "passive"))
      (node (ref "R23") (pin "1") (pinfunction "1_1") (pintype "passive"))
      (node (ref "R27") (pin "1") (pinfunction "1_1") (pintype "passive"))
      (node (ref "R31") (pin "1") (pinfunction "1_1") (pintype "passive"))
      (node (ref "R34") (pin "1") (pinfunction "1_1") (pintype "passive"))
      (node (ref "R36") (pin "1") (pinfunction "1_1") (pintype "passive"))
      (node (ref "R43") (pin "1") (pinfunction "1_1") (pintype "passive"))
      (node (ref "U$1") (pin "1") (pinfunction "VBAT_1") (pintype "power_in"))
      (node (ref "U$1") (pin "13") (pinfunction "VDD_A_13") (pintype "power_in"))
      (node (ref "U$1") (pin "19") (pinfunction "VDD_4_19") (pintype "power_in"))
      (node (ref "U$1") (pin "32") (pinfunction "VDD_1_32") (pintype "power_in"))
      (node (ref "U$1") (pin "48") (pinfunction "VDD_2_48") (pintype "power_in"))
      (node (ref "U$1") (pin "64") (pinfunction "VDD_3_64") (pintype "power_in"))
      (node (ref "U2") (pin "1") (pinfunction "VDD_1") (pintype "bidirectional"))
      (node (ref "U2") (pin "6") (pinfunction "VSS_6") (pintype "bidirectional"))
    )
    (net (code "2") (name "+5V") (class "Default")
      (node (ref "C11") (pin "1") (pinfunction "1_1") (pintype "passive"))
      (node (ref "C18") (pin "1") (pinfunction "1_1") (pintype "passive"))
      (node (ref "C23") (pin "1") (pinfunction "1_1") (pintype "passive"))
      (node (ref "C24") (pin "+") (pinfunction "+_+") (pintype "passive"))
      (node (ref "IC1") (pin "3") (pinfunction "IN_3") (pintype "input"))
      (node (ref "JP1") (pin "2") (pinfunction "2_2") (pintype "passive"))
      (node (ref "JP2") (pin "1") (pinfunction "1_1") (pintype "passive"))
      (node (ref "R32") (pin "2") (pinfunction "2_2") (pintype "passive"))
      (node (ref "U$13") (pin "5") (pinfunction "VBUS_5") (pintype "bidirectional"))
    )
    (net (code "3") (name "/ADXL345_INT1") (class "Default")
      (node (ref "U$1") (pin "10") (pinfunction "PC2_10") (pintype "bidirectional"))
      (node (ref "U2") (pin "8") (pinfunction "INT1_8") (pintype "bidirectional"))
    )
    (net (code "4") (name "/ADXL345_INT2") (class "Default")
      (node (ref "U$1") (pin "9") (pinfunction "PC1_9") (pintype "bidirectional"))
      (node (ref "U2") (pin "9") (pinfunction "INT2_9") (pintype "bidirectional"))
    )
    (net (code "5") (name "/ARCDOZEN_1") (class "Default")
      (node (ref "HOUR0") (pin "C") (pinfunction "C_C") (pintype "passive"))
      (node (ref "MIN0") (pin "C") (pinfunction "C_C") (pintype "passive"))
      (node (ref "MIN1") (pin "C") (pinfunction "C_C") (pintype "passive"))
      (node (ref "MIN2") (pin "C") (pinfunction "C_C") (pintype "passive"))
      (node (ref "MIN3") (pin "C") (pinfunction "C_C") (pintype "passive"))
      (node (ref "MIN4") (pin "C") (pinfunction "C_C") (pintype "passive"))
      (node (ref "SEC0") (pin "C") (pinfunction "C_C") (pintype "passive"))
      (node (ref "SEC1") (pin "C") (pinfunction "C_C") (pintype "passive"))
      (node (ref "SEC2") (pin "C") (pinfunction "C_C") (pintype "passive"))
      (node (ref "SEC3") (pin "C") (pinfunction "C_C") (pintype "passive"))
      (node (ref "SEC4") (pin "C") (pinfunction "C_C") (pintype "passive"))
      (node (ref "SPECIAL0") (pin "C") (pinfunction "C_C") (pintype "passive"))
      (node (ref "U$1") (pin "27") (pinfunction "PB1_27") (pintype "bidirectional"))
    )
    (net (code "6") (name "/ARCDOZEN_2") (class "Default")
      (node (ref "HOUR1") (pin "C") (pinfunction "C_C") (pintype "passive"))
      (node (ref "MIN5") (pin "C") (pinfunction "C_C") (pintype "passive"))
      (node (ref "MIN6") (pin "C") (pinfunction "C_C") (pintype "passive"))
      (node (ref "MIN7") (pin "C") (pinfunction "C_C") (pintype "passive"))
      (node (ref "MIN8") (pin "C") (pinfunction "C_C") (pintype "passive"))
      (node (ref "MIN9") (pin "C") (pinfunction "C_C") (pintype "passive"))
      (node (ref "SEC5") (pin "C") (pinfunction "C_C") (pintype "passive"))
      (node (ref "SEC6") (pin "C") (pinfunction "C_C") (pintype "passive"))
      (node (ref "SEC7") (pin "C") (pinfunction "C_C") (pintype "passive"))
      (node (ref "SEC8") (pin "C") (pinfunction "C_C") (pintype "passive"))
      (node (ref "SEC9") (pin "C") (pinfunction "C_C") (pintype "passive"))
      (node (ref "U$1") (pin "26") (pinfunction "PB0_26") (pintype "bidirectional"))
    )
    (net (code "7") (name "/ARCDOZEN_3") (class "Default")
      (node (ref "HOUR2") (pin "C") (pinfunction "C_C") (pintype "passive"))
      (node (ref "MIN10") (pin "C") (pinfunction "C_C") (pintype "passive"))
      (node (ref "MIN11") (pin "C") (pinfunction "C_C") (pintype "passive"))
      (node (ref "MIN12") (pin "C") (pinfunction "C_C") (pintype "passive"))
      (node (ref "MIN13") (pin "C") (pinfunction "C_C") (pintype "passive"))
      (node (ref "MIN14") (pin "C") (pinfunction "C_C") (pintype "passive"))
      (node (ref "SEC10") (pin "C") (pinfunction "C_C") (pintype "passive"))
      (node (ref "SEC11") (pin "C") (pinfunction "C_C") (pintype "passive"))
      (node (ref "SEC12") (pin "C") (pinfunction "C_C") (pintype "passive"))
      (node (ref "SEC13") (pin "C") (pinfunction "C_C") (pintype "passive"))
      (node (ref "SEC14") (pin "C") (pinfunction "C_C") (pintype "passive"))
      (node (ref "U$1") (pin "17") (pinfunction "PA3_17") (pintype "bidirectional"))
    )
    (net (code "8") (name "/ARCDOZEN_4") (class "Default")
      (node (ref "HOUR3") (pin "C") (pinfunction "C_C") (pintype "passive"))
      (node (ref "MIN15") (pin "C") (pinfunction "C_C") (pintype "passive"))
      (node (ref "MIN16") (pin "C") (pinfunction "C_C") (pintype "passive"))
      (node (ref "MIN17") (pin "C") (pinfunction "C_C") (pintype "passive"))
      (node (ref "MIN18") (pin "C") (pinfunction "C_C") (pintype "passive"))
      (node (ref "MIN19") (pin "C") (pinfunction "C_C") (pintype "passive"))
      (node (ref "SEC15") (pin "C") (pinfunction "C_C") (pintype "passive"))
      (node (ref "SEC16") (pin "C") (pinfunction "C_C") (pintype "passive"))
      (node (ref "SEC17") (pin "C") (pinfunction "C_C") (pintype "passive"))
      (node (ref "SEC18") (pin "C") (pinfunction "C_C") (pintype "passive"))
      (node (ref "SEC19") (pin "C") (pinfunction "C_C") (pintype "passive"))
      (node (ref "SPECIAL3") (pin "C") (pinfunction "C_C") (pintype "passive"))
      (node (ref "U$1") (pin "16") (pinfunction "PA2_16") (pintype "bidirectional"))
    )
    (net (code "9") (name "/ARCDOZEN_5") (class "Default")
      (node (ref "HOUR4") (pin "C") (pinfunction "C_C") (pintype "passive"))
      (node (ref "MIN20") (pin "C") (pinfunction "C_C") (pintype "passive"))
      (node (ref "MIN21") (pin "C") (pinfunction "C_C") (pintype "passive"))
      (node (ref "MIN22") (pin "C") (pinfunction "C_C") (pintype "passive"))
      (node (ref "MIN23") (pin "C") (pinfunction "C_C") (pintype "passive"))
      (node (ref "MIN24") (pin "C") (pinfunction "C_C") (pintype "passive"))
      (node (ref "SEC20") (pin "C") (pinfunction "C_C") (pintype "passive"))
      (node (ref "SEC21") (pin "C") (pinfunction "C_C") (pintype "passive"))
      (node (ref "SEC22") (pin "C") (pinfunction "C_C") (pintype "passive"))
      (node (ref "SEC23") (pin "C") (pinfunction "C_C") (pintype "passive"))
      (node (ref "SEC24") (pin "C") (pinfunction "C_C") (pintype "passive"))
      (node (ref "U$1") (pin "15") (pinfunction "PA1_15") (pintype "bidirectional"))
    )
    (net (code "10") (name "/ARCDOZEN_6") (class "Default")
      (node (ref "HOUR5") (pin "C") (pinfunction "C_C") (pintype "passive"))
      (node (ref "MIN25") (pin "C") (pinfunction "C_C") (pintype "passive"))
      (node (ref "MIN26") (pin "C") (pinfunction "C_C") (pintype "passive"))
      (node (ref "MIN27") (pin "C") (pinfunction "C_C") (pintype "passive"))
      (node (ref "MIN28") (pin "C") (pinfunction "C_C") (pintype "passive"))
      (node (ref "MIN29") (pin "C") (pinfunction "C_C") (pintype "passive"))
      (node (ref "SEC25") (pin "C") (pinfunction "C_C") (pintype "passive"))
      (node (ref "SEC26") (pin "C") (pinfunction "C_C") (pintype "passive"))
      (node (ref "SEC27") (pin "C") (pinfunction "C_C") (pintype "passive"))
      (node (ref "SEC28") (pin "C") (pinfunction "C_C") (pintype "passive"))
      (node (ref "SEC29") (pin "C") (pinfunction "C_C") (pintype "passive"))
      (node (ref "SPECIAL5") (pin "C") (pinfunction "C_C") (pintype "passive"))
      (node (ref "U$1") (pin "14") (pinfunction "PA0_WKUP_14") (pintype "bidirectional"))
    )
    (net (code "11") (name "/ARCDOZEN_7") (class "Default")
      (node (ref "HOUR6") (pin "C") (pinfunction "C_C") (pintype "passive"))
      (node (ref "MIN30") (pin "C") (pinfunction "C_C") (pintype "passive"))
      (node (ref "MIN31") (pin "C") (pinfunction "C_C") (pintype "passive"))
      (node (ref "MIN32") (pin "C") (pinfunction "C_C") (pintype "passive"))
      (node (ref "MIN33") (pin "C") (pinfunction "C_C") (pintype "passive"))
      (node (ref "MIN34") (pin "C") (pinfunction "C_C") (pintype "passive"))
      (node (ref "SEC30") (pin "C") (pinfunction "C_C") (pintype "passive"))
      (node (ref "SEC31") (pin "C") (pinfunction "C_C") (pintype "passive"))
      (node (ref "SEC32") (pin "C") (pinfunction "C_C") (pintype "passive"))
      (node (ref "SEC33") (pin "C") (pinfunction "C_C") (pintype "passive"))
      (node (ref "SEC34") (pin "C") (pinfunction "C_C") (pintype "passive"))
      (node (ref "SPECIAL6") (pin "C") (pinfunction "C_C") (pintype "passive"))
      (node (ref "U$1") (pin "62") (pinfunction "PB9_62") (pintype "input"))
    )
    (net (code "12") (name "/ARCDOZEN_8") (class "Default")
      (node (ref "HOUR7") (pin "C") (pinfunction "C_C") (pintype "passive"))
      (node (ref "MIN35") (pin "C") (pinfunction "C_C") (pintype "passive"))
      (node (ref "MIN36") (pin "C") (pinfunction "C_C") (pintype "passive"))
      (node (ref "MIN37") (pin "C") (pinfunction "C_C") (pintype "passive"))
      (node (ref "MIN38") (pin "C") (pinfunction "C_C") (pintype "passive"))
      (node (ref "MIN39") (pin "C") (pinfunction "C_C") (pintype "passive"))
      (node (ref "SEC35") (pin "C") (pinfunction "C_C") (pintype "passive"))
      (node (ref "SEC36") (pin "C") (pinfunction "C_C") (pintype "passive"))
      (node (ref "SEC37") (pin "C") (pinfunction "C_C") (pintype "passive"))
      (node (ref "SEC38") (pin "C") (pinfunction "C_C") (pintype "passive"))
      (node (ref "SEC39") (pin "C") (pinfunction "C_C") (pintype "passive"))
      (node (ref "U$1") (pin "61") (pinfunction "PB8_61") (pintype "bidirectional"))
    )
    (net (code "13") (name "/ARCDOZEN_9") (class "Default")
      (node (ref "HOUR8") (pin "C") (pinfunction "C_C") (pintype "passive"))
      (node (ref "MIN40") (pin "C") (pinfunction "C_C") (pintype "passive"))
      (node (ref "MIN41") (pin "C") (pinfunction "C_C") (pintype "passive"))
      (node (ref "MIN42") (pin "C") (pinfunction "C_C") (pintype "passive"))
      (node (ref "MIN43") (pin "C") (pinfunction "C_C") (pintype "passive"))
      (node (ref "MIN44") (pin "C") (pinfunction "C_C") (pintype "passive"))
      (node (ref "SEC40") (pin "C") (pinfunction "C_C") (pintype "passive"))
      (node (ref "SEC41") (pin "C") (pinfunction "C_C") (pintype "passive"))
      (node (ref "SEC42") (pin "C") (pinfunction "C_C") (pintype "passive"))
      (node (ref "SEC43") (pin "C") (pinfunction "C_C") (pintype "passive"))
      (node (ref "SEC44") (pin "C") (pinfunction "C_C") (pintype "passive"))
      (node (ref "U$1") (pin "59") (pinfunction "PB7_59") (pintype "bidirectional"))
    )
    (net (code "14") (name "/ARCDOZEN_10") (class "Default")
      (node (ref "HOUR9") (pin "C") (pinfunction "C_C") (pintype "passive"))
      (node (ref "MIN45") (pin "C") (pinfunction "C_C") (pintype "passive"))
      (node (ref "MIN46") (pin "C") (pinfunction "C_C") (pintype "passive"))
      (node (ref "MIN47") (pin "C") (pinfunction "C_C") (pintype "passive"))
      (node (ref "MIN48") (pin "C") (pinfunction "C_C") (pintype "passive"))
      (node (ref "MIN49") (pin "C") (pinfunction "C_C") (pintype "passive"))
      (node (ref "SEC45") (pin "C") (pinfunction "C_C") (pintype "passive"))
      (node (ref "SEC46") (pin "C") (pinfunction "C_C") (pintype "passive"))
      (node (ref "SEC47") (pin "C") (pinfunction "C_C") (pintype "passive"))
      (node (ref "SEC48") (pin "C") (pinfunction "C_C") (pintype "passive"))
      (node (ref "SEC49") (pin "C") (pinfunction "C_C") (pintype "passive"))
      (node (ref "SPECIAL9") (pin "C") (pinfunction "C_C") (pintype "passive"))
      (node (ref "U$1") (pin "58") (pinfunction "PB6_58") (pintype "input"))
    )
    (net (code "15") (name "/ARCDOZEN_11") (class "Default")
      (node (ref "HOUR10") (pin "C") (pinfunction "C_C") (pintype "passive"))
      (node (ref "MIN50") (pin "C") (pinfunction "C_C") (pintype "passive"))
      (node (ref "MIN51") (pin "C") (pinfunction "C_C") (pintype "passive"))
      (node (ref "MIN52") (pin "C") (pinfunction "C_C") (pintype "passive"))
      (node (ref "MIN53") (pin "C") (pinfunction "C_C") (pintype "passive"))
      (node (ref "MIN54") (pin "C") (pinfunction "C_C") (pintype "passive"))
      (node (ref "SEC50") (pin "C") (pinfunction "C_C") (pintype "passive"))
      (node (ref "SEC51") (pin "C") (pinfunction "C_C") (pintype "passive"))
      (node (ref "SEC52") (pin "C") (pinfunction "C_C") (pintype "passive"))
      (node (ref "SEC53") (pin "C") (pinfunction "C_C") (pintype "passive"))
      (node (ref "SEC54") (pin "C") (pinfunction "C_C") (pintype "passive"))
      (node (ref "U$1") (pin "38") (pinfunction "PC7_38") (pintype "bidirectional"))
    )
    (net (code "16") (name "/ARCDOZEN_12") (class "Default")
      (node (ref "HOUR11") (pin "C") (pinfunction "C_C") (pintype "passive"))
      (node (ref "MIN55") (pin "C") (pinfunction "C_C") (pintype "passive"))
      (node (ref "MIN56") (pin "C") (pinfunction "C_C") (pintype "passive"))
      (node (ref "MIN57") (pin "C") (pinfunction "C_C") (pintype "passive"))
      (node (ref "MIN58") (pin "C") (pinfunction "C_C") (pintype "passive"))
      (node (ref "MIN59") (pin "C") (pinfunction "C_C") (pintype "passive"))
      (node (ref "SEC55") (pin "C") (pinfunction "C_C") (pintype "passive"))
      (node (ref "SEC56") (pin "C") (pinfunction "C_C") (pintype "passive"))
      (node (ref "SEC57") (pin "C") (pinfunction "C_C") (pintype "passive"))
      (node (ref "SEC58") (pin "C") (pinfunction "C_C") (pintype "passive"))
      (node (ref "SEC59") (pin "C") (pinfunction "C_C") (pintype "passive"))
      (node (ref "SPECIAL11") (pin "C") (pinfunction "C_C") (pintype "passive"))
      (node (ref "U$1") (pin "37") (pinfunction "PC6_37") (pintype "bidirectional"))
    )
    (net (code "17") (name "/DOZEN1") (class "Default")
      (node (ref "HOUR0") (pin "A") (pinfunction "A_A") (pintype "passive"))
      (node (ref "HOUR1") (pin "A") (pinfunction "A_A") (pintype "passive"))
      (node (ref "HOUR10") (pin "A") (pinfunction "A_A") (pintype "passive"))
      (node (ref "HOUR11") (pin "A") (pinfunction "A_A") (pintype "passive"))
      (node (ref "HOUR2") (pin "A") (pinfunction "A_A") (pintype "passive"))
      (node (ref "HOUR3") (pin "A") (pinfunction "A_A") (pintype "passive"))
      (node (ref "HOUR4") (pin "A") (pinfunction "A_A") (pintype "passive"))
      (node (ref "HOUR5") (pin "A") (pinfunction "A_A") (pintype "passive"))
      (node (ref "HOUR6") (pin "A") (pinfunction "A_A") (pintype "passive"))
      (node (ref "HOUR7") (pin "A") (pinfunction "A_A") (pintype "passive"))
      (node (ref "HOUR8") (pin "A") (pinfunction "A_A") (pintype "passive"))
      (node (ref "HOUR9") (pin "A") (pinfunction "A_A") (pintype "passive"))
      (node (ref "R1") (pin "1") (pinfunction "1_1") (pintype "passive"))
    )
    (net (code "18") (name "/DOZEN2") (class "Default")
      (node (ref "MIN0") (pin "A") (pinfunction "A_A") (pintype "passive"))
      (node (ref "MIN10") (pin "A") (pinfunction "A_A") (pintype "passive"))
      (node (ref "MIN15") (pin "A") (pinfunction "A_A") (pintype "passive"))
      (node (ref "MIN20") (pin "A") (pinfunction "A_A") (pintype "passive"))
      (node (ref "MIN25") (pin "A") (pinfunction "A_A") (pintype "passive"))
      (node (ref "MIN30") (pin "A") (pinfunction "A_A") (pintype "passive"))
      (node (ref "MIN35") (pin "A") (pinfunction "A_A") (pintype "passive"))
      (node (ref "MIN40") (pin "A") (pinfunction "A_A") (pintype "passive"))
      (node (ref "MIN45") (pin "A") (pinfunction "A_A") (pintype "passive"))
      (node (ref "MIN5") (pin "A") (pinfunction "A_A") (pintype "passive"))
      (node (ref "MIN50") (pin "A") (pinfunction "A_A") (pintype "passive"))
      (node (ref "MIN55") (pin "A") (pinfunction "A_A") (pintype "passive"))
      (node (ref "R2") (pin "1") (pinfunction "1_1") (pintype "passive"))
    )
    (net (code "19") (name "/DOZEN3") (class "Default")
      (node (ref "MIN1") (pin "A") (pinfunction "A_A") (pintype "passive"))
      (node (ref "MIN11") (pin "A") (pinfunction "A_A") (pintype "passive"))
      (node (ref "MIN16") (pin "A") (pinfunction "A_A") (pintype "passive"))
      (node (ref "MIN21") (pin "A") (pinfunction "A_A") (pintype "passive"))
      (node (ref "MIN26") (pin "A") (pinfunction "A_A") (pintype "passive"))
      (node (ref "MIN31") (pin "A") (pinfunction "A_A") (pintype "passive"))
      (node (ref "MIN36") (pin "A") (pinfunction "A_A") (pintype "passive"))
      (node (ref "MIN41") (pin "A") (pinfunction "A_A") (pintype "passive"))
      (node (ref "MIN46") (pin "A") (pinfunction "A_A") (pintype "passive"))
      (node (ref "MIN51") (pin "A") (pinfunction "A_A") (pintype "passive"))
      (node (ref "MIN56") (pin "A") (pinfunction "A_A") (pintype "passive"))
      (node (ref "MIN6") (pin "A") (pinfunction "A_A") (pintype "passive"))
      (node (ref "R3") (pin "1") (pinfunction "1_1") (pintype "passive"))
    )
    (net (code "20") (name "/DOZEN4") (class "Default")
      (node (ref "MIN12") (pin "A") (pinfunction "A_A") (pintype "passive"))
      (node (ref "MIN17") (pin "A") (pinfunction "A_A") (pintype "passive"))
      (node (ref "MIN2") (pin "A") (pinfunction "A_A") (pintype "passive"))
      (node (ref "MIN22") (pin "A") (pinfunction "A_A") (pintype "passive"))
      (node (ref "MIN27") (pin "A") (pinfunction "A_A") (pintype "passive"))
      (node (ref "MIN32") (pin "A") (pinfunction "A_A") (pintype "passive"))
      (node (ref "MIN37") (pin "A") (pinfunction "A_A") (pintype "passive"))
      (node (ref "MIN42") (pin "A") (pinfunction "A_A") (pintype "passive"))
      (node (ref "MIN47") (pin "A") (pinfunction "A_A") (pintype "passive"))
      (node (ref "MIN52") (pin "A") (pinfunction "A_A") (pintype "passive"))
      (node (ref "MIN57") (pin "A") (pinfunction "A_A") (pintype "passive"))
      (node (ref "MIN7") (pin "A") (pinfunction "A_A") (pintype "passive"))
      (node (ref "R4") (pin "1") (pinfunction "1_1") (pintype "passive"))
    )
    (net (code "21") (name "/DOZEN5") (class "Default")
      (node (ref "MIN13") (pin "A") (pinfunction "A_A") (pintype "passive"))
      (node (ref "MIN18") (pin "A") (pinfunction "A_A") (pintype "passive"))
      (node (ref "MIN23") (pin "A") (pinfunction "A_A") (pintype "passive"))
      (node (ref "MIN28") (pin "A") (pinfunction "A_A") (pintype "passive"))
      (node (ref "MIN3") (pin "A") (pinfunction "A_A") (pintype "passive"))
      (node (ref "MIN33") (pin "A") (pinfunction "A_A") (pintype "passive"))
      (node (ref "MIN38") (pin "A") (pinfunction "A_A") (pintype "passive"))
      (node (ref "MIN43") (pin "A") (pinfunction "A_A") (pintype "passive"))
      (node (ref "MIN48") (pin "A") (pinfunction "A_A") (pintype "passive"))
      (node (ref "MIN53") (pin "A") (pinfunction "A_A") (pintype "passive"))
      (node (ref "MIN58") (pin "A") (pinfunction "A_A") (pintype "passive"))
      (node (ref "MIN8") (pin "A") (pinfunction "A_A") (pintype "passive"))
      (node (ref "R5") (pin "1") (pinfunction "1_1") (pintype "passive"))
    )
    (net (code "22") (name "/DOZEN6") (class "Default")
      (node (ref "MIN14") (pin "A") (pinfunction "A_A") (pintype "passive"))
      (node (ref "MIN19") (pin "A") (pinfunction "A_A") (pintype "passive"))
      (node (ref "MIN24") (pin "A") (pinfunction "A_A") (pintype "passive"))
      (node (ref "MIN29") (pin "A") (pinfunction "A_A") (pintype "passive"))
      (node (ref "MIN34") (pin "A") (pinfunction "A_A") (pintype "passive"))
      (node (ref "MIN39") (pin "A") (pinfunction "A_A") (pintype "passive"))
      (node (ref "MIN4") (pin "A") (pinfunction "A_A") (pintype "passive"))
      (node (ref "MIN44") (pin "A") (pinfunction "A_A") (pintype "passive"))
      (node (ref "MIN49") (pin "A") (pinfunction "A_A") (pintype "passive"))
      (node (ref "MIN54") (pin "A") (pinfunction "A_A") (pintype "passive"))
      (node (ref "MIN59") (pin "A") (pinfunction "A_A") (pintype "passive"))
      (node (ref "MIN9") (pin "A") (pinfunction "A_A") (pintype "passive"))
      (node (ref "R6") (pin "1") (pinfunction "1_1") (pintype "passive"))
    )
    (net (code "23") (name "/DOZEN7") (class "Default")
      (node (ref "R7") (pin "1") (pinfunction "1_1") (pintype "passive"))
      (node (ref "SEC0") (pin "A") (pinfunction "A_A") (pintype "passive"))
      (node (ref "SEC10") (pin "A") (pinfunction "A_A") (pintype "passive"))
      (node (ref "SEC15") (pin "A") (pinfunction "A_A") (pintype "passive"))
      (node (ref "SEC20") (pin "A") (pinfunction "A_A") (pintype "passive"))
      (node (ref "SEC25") (pin "A") (pinfunction "A_A") (pintype "passive"))
      (node (ref "SEC30") (pin "A") (pinfunction "A_A") (pintype "passive"))
      (node (ref "SEC35") (pin "A") (pinfunction "A_A") (pintype "passive"))
      (node (ref "SEC40") (pin "A") (pinfunction "A_A") (pintype "passive"))
      (node (ref "SEC45") (pin "A") (pinfunction "A_A") (pintype "passive"))
      (node (ref "SEC5") (pin "A") (pinfunction "A_A") (pintype "passive"))
      (node (ref "SEC50") (pin "A") (pinfunction "A_A") (pintype "passive"))
      (node (ref "SEC55") (pin "A") (pinfunction "A_A") (pintype "passive"))
    )
    (net (code "24") (name "/DOZEN8") (class "Default")
      (node (ref "R8") (pin "1") (pinfunction "1_1") (pintype "passive"))
      (node (ref "SEC1") (pin "A") (pinfunction "A_A") (pintype "passive"))
      (node (ref "SEC11") (pin "A") (pinfunction "A_A") (pintype "passive"))
      (node (ref "SEC16") (pin "A") (pinfunction "A_A") (pintype "passive"))
      (node (ref "SEC21") (pin "A") (pinfunction "A_A") (pintype "passive"))
      (node (ref "SEC26") (pin "A") (pinfunction "A_A") (pintype "passive"))
      (node (ref "SEC31") (pin "A") (pinfunction "A_A") (pintype "passive"))
      (node (ref "SEC36") (pin "A") (pinfunction "A_A") (pintype "passive"))
      (node (ref "SEC41") (pin "A") (pinfunction "A_A") (pintype "passive"))
      (node (ref "SEC46") (pin "A") (pinfunction "A_A") (pintype "passive"))
      (node (ref "SEC51") (pin "A") (pinfunction "A_A") (pintype "passive"))
      (node (ref "SEC56") (pin "A") (pinfunction "A_A") (pintype "passive"))
      (node (ref "SEC6") (pin "A") (pinfunction "A_A") (pintype "passive"))
    )
    (net (code "25") (name "/DOZEN9") (class "Default")
      (node (ref "R9") (pin "1") (pinfunction "1_1") (pintype "passive"))
      (node (ref "SEC12") (pin "A") (pinfunction "A_A") (pintype "passive"))
      (node (ref "SEC17") (pin "A") (pinfunction "A_A") (pintype "passive"))
      (node (ref "SEC2") (pin "A") (pinfunction "A_A") (pintype "passive"))
      (node (ref "SEC22") (pin "A") (pinfunction "A_A") (pintype "passive"))
      (node (ref "SEC27") (pin "A") (pinfunction "A_A") (pintype "passive"))
      (node (ref "SEC32") (pin "A") (pinfunction "A_A") (pintype "passive"))
      (node (ref "SEC37") (pin "A") (pinfunction "A_A") (pintype "passive"))
      (node (ref "SEC42") (pin "A") (pinfunction "A_A") (pintype "passive"))
      (node (ref "SEC47") (pin "A") (pinfunction "A_A") (pintype "passive"))
      (node (ref "SEC52") (pin "A") (pinfunction "A_A") (pintype "passive"))
      (node (ref "SEC57") (pin "A") (pinfunction "A_A") (pintype "passive"))
      (node (ref "SEC7") (pin "A") (pinfunction "A_A") (pintype "passive"))
    )
    (net (code "26") (name "/DOZEN10") (class "Default")
      (node (ref "R10") (pin "1") (pinfunction "1_1") (pintype "passive"))
      (node (ref "SEC13") (pin "A") (pinfunction "A_A") (pintype "passive"))
      (node (ref "SEC18") (pin "A") (pinfunction "A_A") (pintype "passive"))
      (node (ref "SEC23") (pin "A") (pinfunction "A_A") (pintype "passive"))
      (node (ref "SEC28") (pin "A") (pinfunction "A_A") (pintype "passive"))
      (node (ref "SEC3") (pin "A") (pinfunction "A_A") (pintype "passive"))
      (node (ref "SEC33") (pin "A") (pinfunction "A_A") (pintype "passive"))
      (node (ref "SEC38") (pin "A") (pinfunction "A_A") (pintype "passive"))
      (node (ref "SEC43") (pin "A") (pinfunction "A_A") (pintype "passive"))
      (node (ref "SEC48") (pin "A") (pinfunction "A_A") (pintype "passive"))
      (node (ref "SEC53") (pin "A") (pinfunction "A_A") (pintype "passive"))
      (node (ref "SEC58") (pin "A") (pinfunction "A_A") (pintype "passive"))
      (node (ref "SEC8") (pin "A") (pinfunction "A_A") (pintype "passive"))
    )
    (net (code "27") (name "/DOZEN11") (class "Default")
      (node (ref "R11") (pin "1") (pinfunction "1_1") (pintype "passive"))
      (node (ref "SEC14") (pin "A") (pinfunction "A_A") (pintype "passive"))
      (node (ref "SEC19") (pin "A") (pinfunction "A_A") (pintype "passive"))
      (node (ref "SEC24") (pin "A") (pinfunction "A_A") (pintype "passive"))
      (node (ref "SEC29") (pin "A") (pinfunction "A_A") (pintype "passive"))
      (node (ref "SEC34") (pin "A") (pinfunction "A_A") (pintype "passive"))
      (node (ref "SEC39") (pin "A") (pinfunction "A_A") (pintype "passive"))
      (node (ref "SEC4") (pin "A") (pinfunction "A_A") (pintype "passive"))
      (node (ref "SEC44") (pin "A") (pinfunction "A_A") (pintype "passive"))
      (node (ref "SEC49") (pin "A") (pinfunction "A_A") (pintype "passive"))
      (node (ref "SEC54") (pin "A") (pinfunction "A_A") (pintype "passive"))
      (node (ref "SEC59") (pin "A") (pinfunction "A_A") (pintype "passive"))
      (node (ref "SEC9") (pin "A") (pinfunction "A_A") (pintype "passive"))
    )
    (net (code "28") (name "/DOZEN12") (class "Default")
      (node (ref "R12") (pin "1") (pinfunction "1_1") (pintype "passive"))
      (node (ref "SPECIAL0") (pin "A") (pinfunction "A_A") (pintype "passive"))
      (node (ref "SPECIAL11") (pin "A") (pinfunction "A_A") (pintype "passive"))
      (node (ref "SPECIAL3") (pin "A") (pinfunction "A_A") (pintype "passive"))
      (node (ref "SPECIAL5") (pin "A") (pinfunction "A_A") (pintype "passive"))
      (node (ref "SPECIAL6") (pin "A") (pinfunction "A_A") (pintype "passive"))
      (node (ref "SPECIAL9") (pin "A") (pinfunction "A_A") (pintype "passive"))
    )
    (net (code "29") (name "/LIGHT_SENSOR") (class "Default")
      (node (ref "R27") (pin "2") (pinfunction "2_2") (pintype "passive"))
      (node (ref "U$1") (pin "8") (pinfunction "PC0_8") (pintype "bidirectional"))
      (node (ref "U$11") (pin "1") (pinfunction "COL_1") (pintype "passive"))
    )
    (net (code "30") (name "/RST") (class "Default")
      (node (ref "R16") (pin "1") (pinfunction "1_1") (pintype "passive"))
      (node (ref "U$1") (pin "7") (pinfunction "NRST_7") (pintype "input"))
    )
    (net (code "31") (name "/SPI1_MISO") (class "Default")
      (node (ref "U$1") (pin "22") (pinfunction "PA6_22") (pintype "bidirectional"))
      (node (ref "U2") (pin "12") (pinfunction "SDO_12") (pintype "bidirectional"))
    )
    (net (code "32") (name "/SPI1_MOSI") (class "Default")
      (node (ref "U$1") (pin "23") (pinfunction "PA7_23") (pintype "bidirectional"))
      (node (ref "U2") (pin "13") (pinfunction "SDA_13") (pintype "bidirectional"))
    )
    (net (code "33") (name "/SPI1_NSS") (class "Default")
      (node (ref "U$1") (pin "20") (pinfunction "PA4_20") (pintype "bidirectional"))
      (node (ref "U2") (pin "7") (pinfunction "CS_7") (pintype "bidirectional"))
    )
    (net (code "34") (name "/SPI1_SCK") (class "Default")
      (node (ref "U$1") (pin "21") (pinfunction "PA5_21") (pintype "bidirectional"))
      (node (ref "U2") (pin "14") (pinfunction "SCL_14") (pintype "bidirectional"))
    )
    (net (code "35") (name "/TCK") (class "Default")
      (node (ref "PROG") (pin "P$2") (pinfunction "2_P$2") (pintype "passive"))
      (node (ref "R23") (pin "2") (pinfunction "2_2") (pintype "passive"))
      (node (ref "U$1") (pin "49") (pinfunction "PA14_49") (pintype "bidirectional"))
    )
    (net (code "36") (name "/TDO") (class "Default")
      (node (ref "PROG") (pin "P$6") (pinfunction "6_P$6") (pintype "passive"))
      (node (ref "R36") (pin "2") (pinfunction "2_2") (pintype "passive"))
      (node (ref "U$1") (pin "55") (pinfunction "PB3_55") (pintype "bidirectional"))
    )
    (net (code "37") (name "/TMS") (class "Default")
      (node (ref "PROG") (pin "P$4") (pinfunction "4_P$4") (pintype "passive"))
      (node (ref "R31") (pin "2") (pinfunction "2_2") (pintype "passive"))
      (node (ref "U$1") (pin "46") (pinfunction "PA13_46") (pintype "bidirectional"))
    )
    (net (code "38") (name "/TOUCH1") (class "Default")
      (node (ref "U$1") (pin "50") (pinfunction "PA15_50") (pintype "bidirectional"))
    )
    (net (code "39") (name "/TOUCH2") (class "Default")
      (node (ref "U$1") (pin "11") (pinfunction "PC3_11") (pintype "bidirectional"))
    )
    (net (code "40") (name "/TOUCH3") (class "Default")
      (node (ref "U$1") (pin "24") (pinfunction "PC4_24") (pintype "bidirectional"))
    )
    (net (code "41") (name "/TOUCH4") (class "Default")
      (node (ref "U$1") (pin "54") (pinfunction "PD2_54") (pintype "bidirectional"))
    )
    (net (code "42") (name "/TOUCH5") (class "Default")
      (node (ref "U$1") (pin "57") (pinfunction "PB5_57") (pintype "input"))
    )
    (net (code "43") (name "/TRST") (class "Default")
      (node (ref "PROG") (pin "P$5") (pinfunction "5_P$5") (pintype "passive"))
      (node (ref "R43") (pin "2") (pinfunction "2_2") (pintype "passive"))
      (node (ref "U$1") (pin "56") (pinfunction "PB4_56") (pintype "bidirectional"))
    )
    (net (code "44") (name "/USART1_RX") (class "Default")
      (node (ref "FTDI") (pin "3") (pinfunction "3_3") (pintype "passive"))
      (node (ref "U$1") (pin "43") (pinfunction "PA10_43") (pintype "bidirectional"))
    )
    (net (code "45") (name "/USART1_TX") (class "Default")
      (node (ref "FTDI") (pin "2") (pinfunction "2_2") (pintype "passive"))
      (node (ref "U$1") (pin "42") (pinfunction "PA9_42") (pintype "input"))
    )
    (net (code "46") (name "/USB_DISCONNECT") (class "Default")
      (node (ref "Q7") (pin "1") (pinfunction "G_1") (pintype "passive"))
      (node (ref "R34") (pin "2") (pinfunction "2_2") (pintype "passive"))
      (node (ref "U$1") (pin "41") (pinfunction "PA8_41") (pintype "bidirectional"))
    )
    (net (code "47") (name "/USB_DM") (class "Default")
      (node (ref "R28") (pin "1") (pinfunction "1_1") (pintype "passive"))
      (node (ref "U$1") (pin "44") (pinfunction "PA11_44") (pintype "bidirectional"))
    )
    (net (code "48") (name "/USB_DP") (class "Default")
      (node (ref "R29") (pin "1") (pinfunction "1_1") (pintype "passive"))
      (node (ref "R30") (pin "2") (pinfunction "2_2") (pintype "passive"))
      (node (ref "U$1") (pin "45") (pinfunction "PA12_45") (pintype "bidirectional"))
    )
    (net (code "49") (name "/WAKE") (class "Default")
      (node (ref "Q1") (pin "1") (pinfunction "G_1") (pintype "passive"))
      (node (ref "U$1") (pin "2") (pinfunction "PC13-TAMPER-RTC_2") (pintype "input"))
    )
    (net (code "50") (name "GND") (class "Default")
      (node (ref "C1") (pin "2") (pinfunction "2_2") (pintype "passive"))
      (node (ref "C11") (pin "2") (pinfunction "2_2") (pintype "passive"))
      (node (ref "C17") (pin "2") (pinfunction "2_2") (pintype "passive"))
      (node (ref "C18") (pin "2") (pinfunction "2_2") (pintype "passive"))
      (node (ref "C2") (pin "2") (pinfunction "2_2") (pintype "passive"))
      (node (ref "C20") (pin "2") (pinfunction "2_2") (pintype "passive"))
      (node (ref "C23") (pin "2") (pinfunction "2_2") (pintype "passive"))
      (node (ref "C24") (pin "-") (pinfunction "-_-") (pintype "passive"))
      (node (ref "C25") (pin "-") (pinfunction "-_-") (pintype "passive"))
      (node (ref "C27") (pin "2") (pinfunction "2_2") (pintype "passive"))
      (node (ref "C3") (pin "2") (pinfunction "2_2") (pintype "passive"))
      (node (ref "C4") (pin "2") (pinfunction "2_2") (pintype "passive"))
      (node (ref "C5") (pin "2") (pinfunction "2_2") (pintype "passive"))
      (node (ref "C6") (pin "1") (pinfunction "1_1") (pintype "passive"))
      (node (ref "C7") (pin "2") (pinfunction "2_2") (pintype "passive"))
      (node (ref "C8") (pin "2") (pinfunction "2_2") (pintype "passive"))
      (node (ref "FTDI") (pin "5") (pinfunction "5_5") (pintype "passive"))
      (node (ref "FTDI") (pin "6") (pinfunction "6_6") (pintype "passive"))
      (node (ref "IC1") (pin "1") (pinfunction "ADJ_1") (pintype "input"))
      (node (ref "PROG") (pin "P$3") (pinfunction "3_P$3") (pintype "passive"))
      (node (ref "Q1") (pin "2") (pinfunction "S_2") (pintype "passive"))
      (node (ref "R33") (pin "1") (pinfunction "1_1") (pintype "passive"))
      (node (ref "U$1") (pin "12") (pinfunction "VSS_A_12") (pintype "power_in"))
      (node (ref "U$1") (pin "18") (pinfunction "VSS_4_18") (pintype "power_in"))
      (node (ref "U$1") (pin "28") (pinfunction "PB2_28") (pintype "bidirectional"))
      (node (ref "U$1") (pin "31") (pinfunction "VSS_1_31") (pintype "power_in"))
      (node (ref "U$1") (pin "47") (pinfunction "VSS_2_47") (pintype "power_in"))
      (node (ref "U$1") (pin "60") (pinfunction "BOOT0_60") (pintype "input"))
      (node (ref "U$1") (pin "63") (pinfunction "VSS_3_63") (pintype "power_in"))
      (node (ref "U$11") (pin "2") (pinfunction "EMI_2") (pintype "passive"))
      (node (ref "U$12") (pin "GND") (pinfunction "GND_GND") (pintype "bidirectional"))
      (node (ref "U$12") (pin "MTN1") (pinfunction "MTN2_MTN1") (pintype "bidirectional"))
      (node (ref "U$12") (pin "MTN2") (pinfunction "MTN3_MTN2") (pintype "bidirectional"))
      (node (ref "U$12") (pin "MTN3") (pinfunction "MTN1_MTN3") (pintype "bidirectional"))
      (node (ref "U$12") (pin "MTN4") (pinfunction "MTN4_MTN4") (pintype "bidirectional"))
      (node (ref "U$13") (pin "2") (pinfunction "GND_2") (pintype "bidirectional"))
      (node (ref "U2") (pin "2") (pinfunction "GND_2") (pintype "bidirectional"))
      (node (ref "U2") (pin "4") (pinfunction "GND_4") (pintype "bidirectional"))
      (node (ref "U2") (pin "5") (pinfunction "GND_5") (pintype "bidirectional"))
      (node (ref "Y1") (pin "2") (pinfunction "2_2") (pintype "passive"))
    )
    (net (code "51") (name "Net-(C6-Pad2)") (class "Default")
      (node (ref "C6") (pin "2") (pinfunction "2_2") (pintype "passive"))
      (node (ref "R13") (pin "1") (pinfunction "1_1") (pintype "passive"))
      (node (ref "U$2") (pin "P$4") (pinfunction "P$4_P$4") (pintype "bidirectional"))
    )
    (net (code "52") (name "Net-(FTDI-Pad4)") (class "Default")
      (node (ref "FTDI") (pin "4") (pinfunction "4_4") (pintype "passive"))
      (node (ref "JP1") (pin "1") (pinfunction "1_1") (pintype "passive"))
    )
    (net (code "53") (name "Net-(JP2-Pad2)") (class "Default")
      (node (ref "JP2") (pin "2") (pinfunction "2_2") (pintype "passive"))
      (node (ref "U$12") (pin "VBUS") (pinfunction "VBUS_VBUS") (pintype "bidirectional"))
    )
    (net (code "54") (name "Net-(Q1-D)") (class "Default")
      (node (ref "FTDI") (pin "1") (pinfunction "1_1") (pintype "passive"))
      (node (ref "Q1") (pin "3") (pinfunction "D_3") (pintype "passive"))
    )
    (net (code "55") (name "Net-(Q6-G)") (class "Default")
      (node (ref "Q6") (pin "1") (pinfunction "G_1") (pintype "passive"))
      (node (ref "Q7") (pin "3") (pinfunction "D_3") (pintype "passive"))
      (node (ref "R32") (pin "1") (pinfunction "1_1") (pintype "passive"))
    )
    (net (code "56") (name "Net-(Q6-S)") (class "Default")
      (node (ref "Q6") (pin "2") (pinfunction "S_2") (pintype "passive"))
      (node (ref "R30") (pin "1") (pinfunction "1_1") (pintype "passive"))
    )
    (net (code "57") (name "Net-(Q7-S)") (class "Default")
      (node (ref "Q7") (pin "2") (pinfunction "S_2") (pintype "passive"))
      (node (ref "R33") (pin "2") (pinfunction "2_2") (pintype "passive"))
    )
    (net (code "58") (name "Net-(U$1-PB10)") (class "Default")
      (node (ref "R1") (pin "2") (pinfunction "2_2") (pintype "passive"))
      (node (ref "U$1") (pin "29") (pinfunction "PB10_29") (pintype "input"))
    )
    (net (code "59") (name "Net-(U$1-PB11)") (class "Default")
      (node (ref "R2") (pin "2") (pinfunction "2_2") (pintype "passive"))
      (node (ref "U$1") (pin "30") (pinfunction "PB11_30") (pintype "input"))
    )
    (net (code "60") (name "Net-(U$1-PB12)") (class "Default")
      (node (ref "R3") (pin "2") (pinfunction "2_2") (pintype "passive"))
      (node (ref "U$1") (pin "33") (pinfunction "PB12_33") (pintype "input"))
    )
    (net (code "61") (name "Net-(U$1-PB13)") (class "Default")
      (node (ref "R4") (pin "2") (pinfunction "2_2") (pintype "passive"))
      (node (ref "U$1") (pin "34") (pinfunction "PB13_34") (pintype "input"))
    )
    (net (code "62") (name "Net-(U$1-PB14)") (class "Default")
      (node (ref "R5") (pin "2") (pinfunction "2_2") (pintype "passive"))
      (node (ref "U$1") (pin "35") (pinfunction "PB14_35") (pintype "input"))
    )
    (net (code "63") (name "Net-(U$1-PB15)") (class "Default")
      (node (ref "R6") (pin "2") (pinfunction "2_2") (pintype "passive"))
      (node (ref "U$1") (pin "36") (pinfunction "PB15_36") (pintype "input"))
    )
    (net (code "64") (name "Net-(U$1-PC5)") (class "Default")
      (node (ref "R12") (pin "2") (pinfunction "2_2") (pintype "passive"))
      (node (ref "U$1") (pin "25") (pinfunction "PC5_25") (pintype "bidirectional"))
    )
    (net (code "65") (name "Net-(U$1-PC8)") (class "Default")
      (node (ref "R8") (pin "2") (pinfunction "2_2") (pintype "passive"))
      (node (ref "U$1") (pin "39") (pinfunction "PC8_39") (pintype "bidirectional"))
    )
    (net (code "66") (name "Net-(U$1-PC9)") (class "Default")
      (node (ref "R7") (pin "2") (pinfunction "2_2") (pintype "passive"))
      (node (ref "U$1") (pin "40") (pinfunction "PC9_40") (pintype "bidirectional"))
    )
    (net (code "67") (name "Net-(U$1-PC10)") (class "Default")
      (node (ref "R11") (pin "2") (pinfunction "2_2") (pintype "passive"))
      (node (ref "U$1") (pin "51") (pinfunction "PC10_51") (pintype "bidirectional"))
    )
    (net (code "68") (name "Net-(U$1-PC11)") (class "Default")
      (node (ref "R10") (pin "2") (pinfunction "2_2") (pintype "passive"))
      (node (ref "U$1") (pin "52") (pinfunction "PC11_52") (pintype "bidirectional"))
    )
    (net (code "69") (name "Net-(U$1-PC12)") (class "Default")
      (node (ref "R9") (pin "2") (pinfunction "2_2") (pintype "passive"))
      (node (ref "U$1") (pin "53") (pinfunction "PC12_53") (pintype "bidirectional"))
    )
    (net (code "70") (name "Net-(U$1-PC14-OSC32_IN)") (class "Default")
      (node (ref "C7") (pin "1") (pinfunction "1_1") (pintype "passive"))
      (node (ref "U$1") (pin "3") (pinfunction "PC14-OSC32_IN_3") (pintype "input"))
      (node (ref "U$2") (pin "P$1") (pinfunction "P$1_P$1") (pintype "bidirectional"))
    )
    (net (code "71") (name "Net-(U$1-PC15-OSC32_OUT)") (class "Default")
      (node (ref "R13") (pin "2") (pinfunction "2_2") (pintype "passive"))
      (node (ref "U$1") (pin "4") (pinfunction "PC15-OSC32_OUT_4") (pintype "input"))
    )
    (net (code "72") (name "Net-(U$1-PD0-OSC_IN)") (class "Default")
      (node (ref "U$1") (pin "5") (pinfunction "PD0-OSC_IN_5") (pintype "input"))
      (node (ref "Y1") (pin "1") (pinfunction "1_1") (pintype "passive"))
    )
    (net (code "73") (name "Net-(U$1-PD1-OSC_OUT)") (class "Default")
      (node (ref "U$1") (pin "6") (pinfunction "PD1-OSC_OUT_6") (pintype "input"))
      (node (ref "Y1") (pin "3") (pinfunction "3_3") (pintype "passive"))
    )
    (net (code "74") (name "Net-(U$13-IO1_IN)") (class "Default")
      (node (ref "U$12") (pin "D-") (pinfunction "D-_D-") (pintype "bidirectional"))
      (node (ref "U$13") (pin "1") (pinfunction "IO1_IN_1") (pintype "bidirectional"))
    )
    (net (code "75") (name "Net-(U$13-IO1_OUT)") (class "Default")
      (node (ref "R28") (pin "2") (pinfunction "2_2") (pintype "passive"))
      (node (ref "U$13") (pin "6") (pinfunction "IO1_OUT_6") (pintype "bidirectional"))
    )
    (net (code "76") (name "Net-(U$13-IO2_IN)") (class "Default")
      (node (ref "U$12") (pin "D+") (pinfunction "D+_D+") (pintype "bidirectional"))
      (node (ref "U$13") (pin "3") (pinfunction "IO2_IN_3") (pintype "bidirectional"))
    )
    (net (code "77") (name "Net-(U$13-IO2_OUT)") (class "Default")
      (node (ref "R29") (pin "2") (pinfunction "2_2") (pintype "passive"))
      (node (ref "U$13") (pin "4") (pinfunction "IO2_OUT_4") (pintype "bidirectional"))
    )
    (net (code "78") (name "unconnected-(U$2-PadP$2)") (class "Default")
      (node (ref "U$2") (pin "P$2") (pinfunction "P$2_P$2") (pintype "bidirectional"))
    )
    (net (code "79") (name "unconnected-(U$2-PadP$3)") (class "Default")
      (node (ref "U$2") (pin "P$3") (pinfunction "P$3_P$3") (pintype "bidirectional"))
    )
    (net (code "80") (name "unconnected-(U$12-PadID)") (class "Default")
      (node (ref "U$12") (pin "ID") (pinfunction "ID_ID") (pintype "bidirectional"))
    )
    (net (code "81") (name "unconnected-(U2-NC-Pad3)") (class "Default")
      (node (ref "U2") (pin "3") (pinfunction "NC_3") (pintype "bidirectional"))
    )
    (net (code "82") (name "unconnected-(U2-NC-Pad10)") (class "Default")
      (node (ref "U2") (pin "10") (pinfunction "NC_10") (pintype "bidirectional"))
    )
    (net (code "83") (name "unconnected-(U2-NC-Pad11)") (class "Default")
      (node (ref "U2") (pin "11") (pinfunction "NC_11") (pintype "bidirectional"))
    )
  )
)
